# uSlices_v3_2.net
KiCad netlist of a schematic drawn in EAGLE
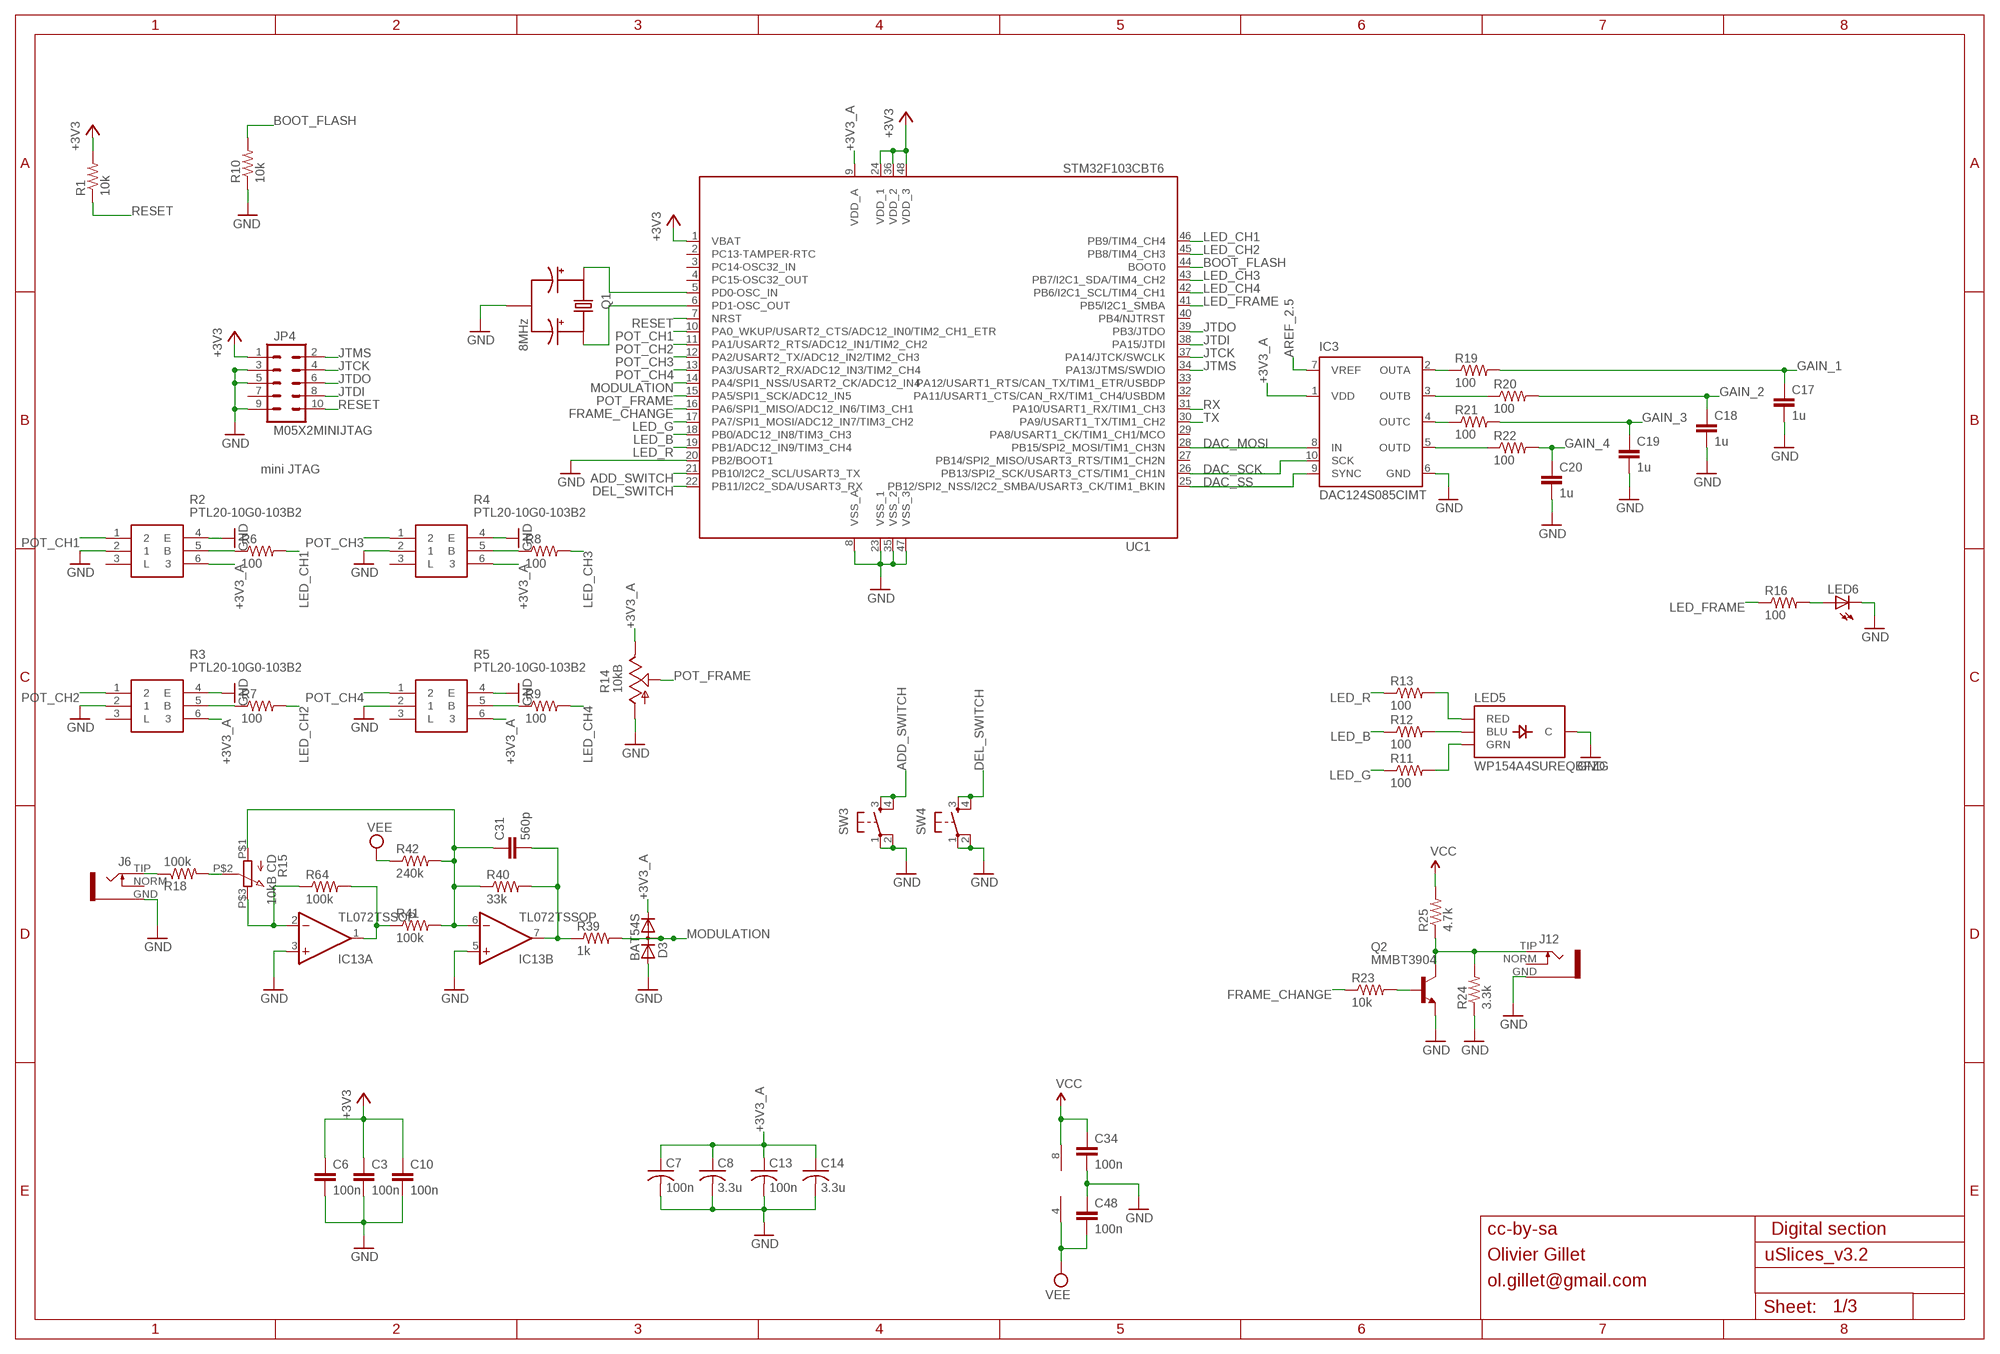
[diagram p0: schematic, sheet 1]
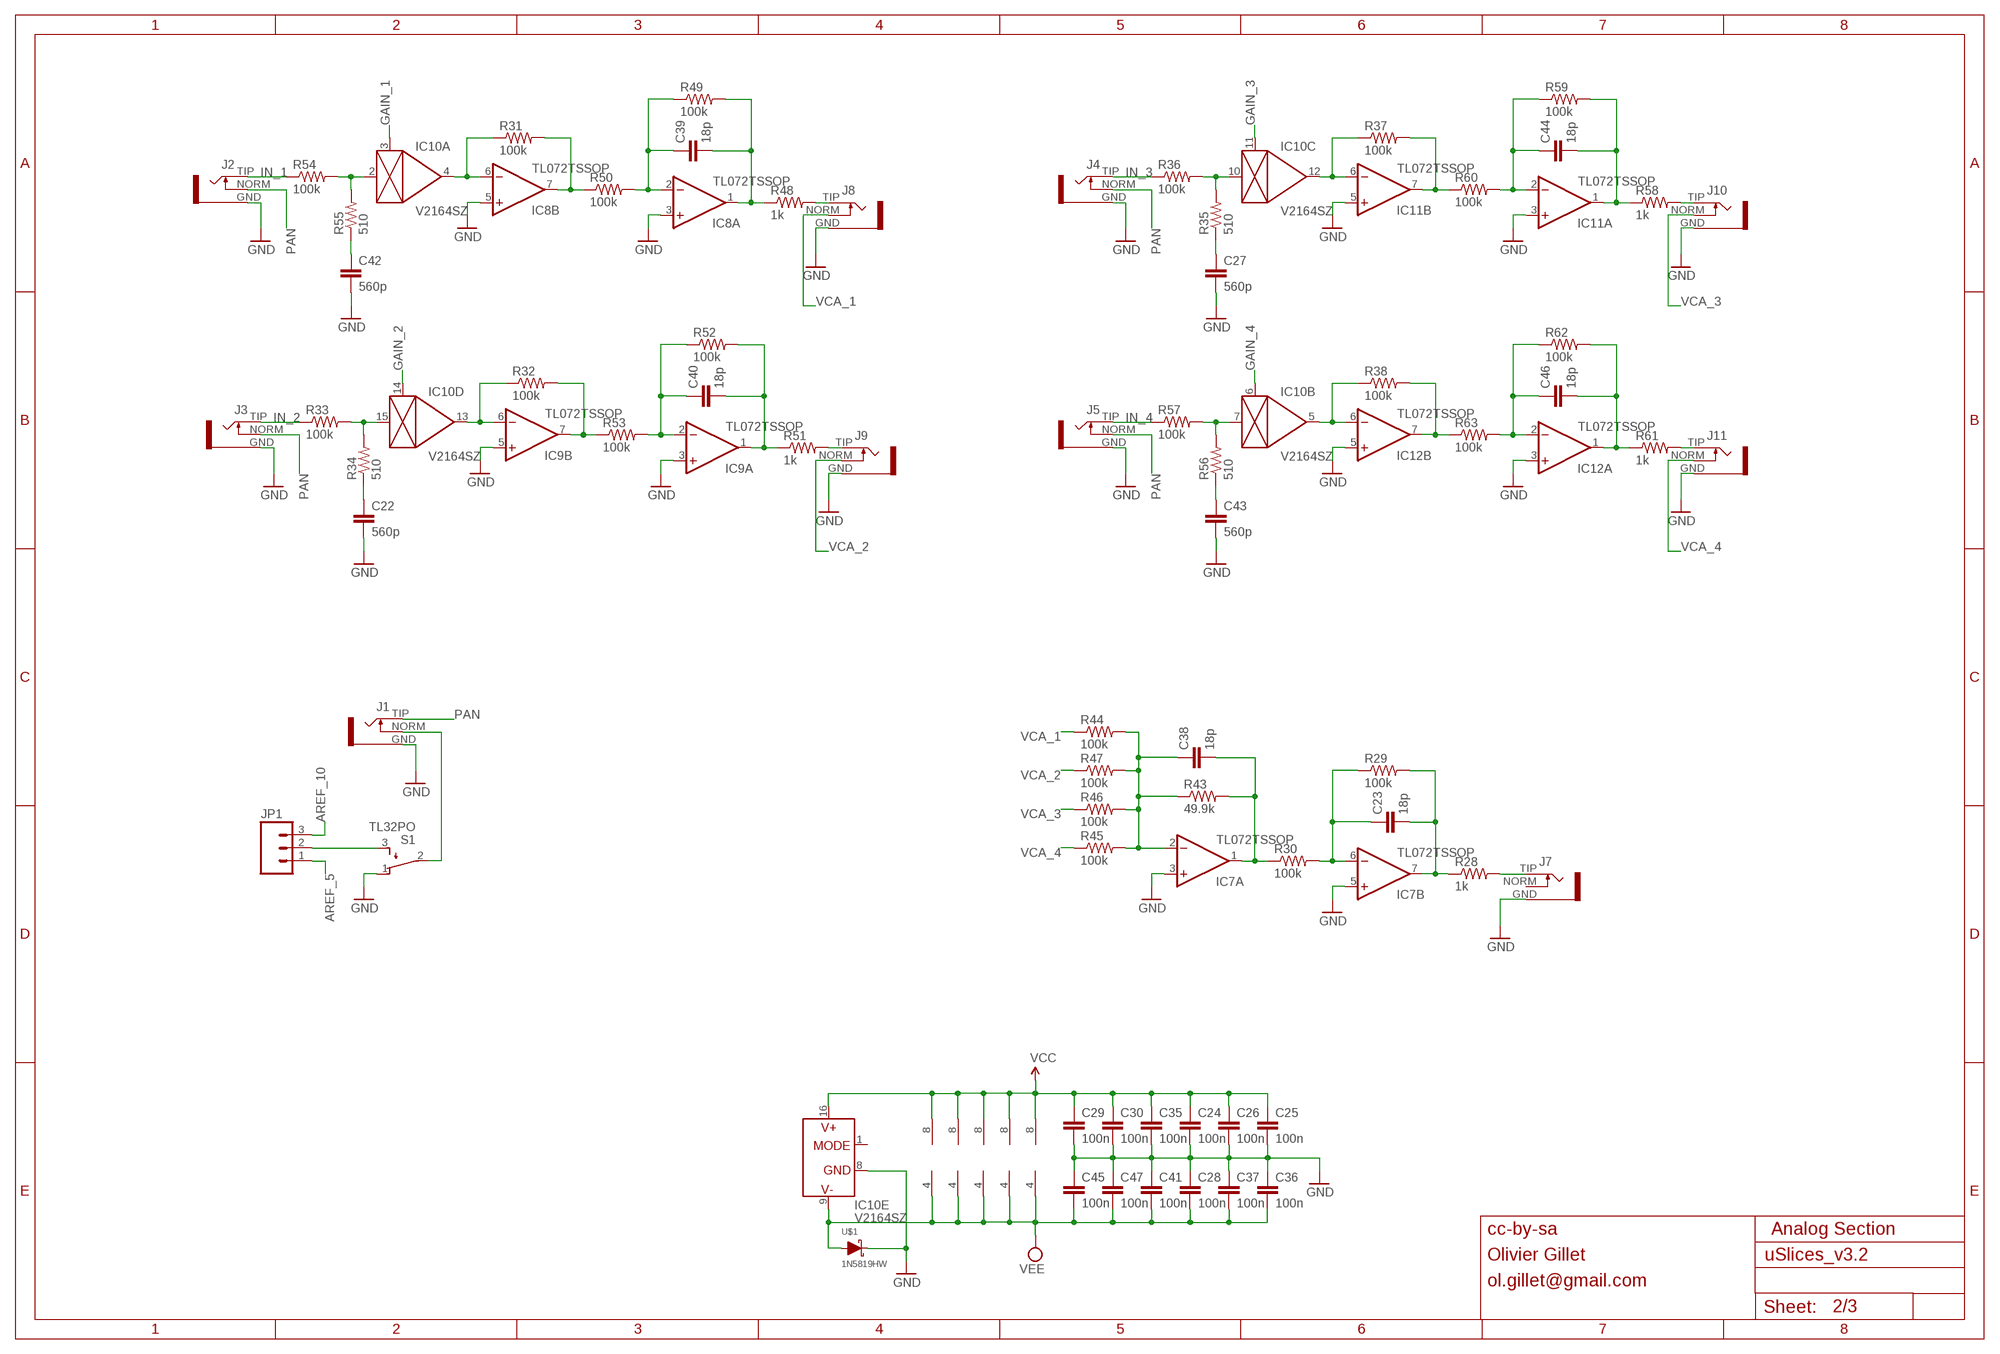
[diagram p1: schematic, sheet 2]
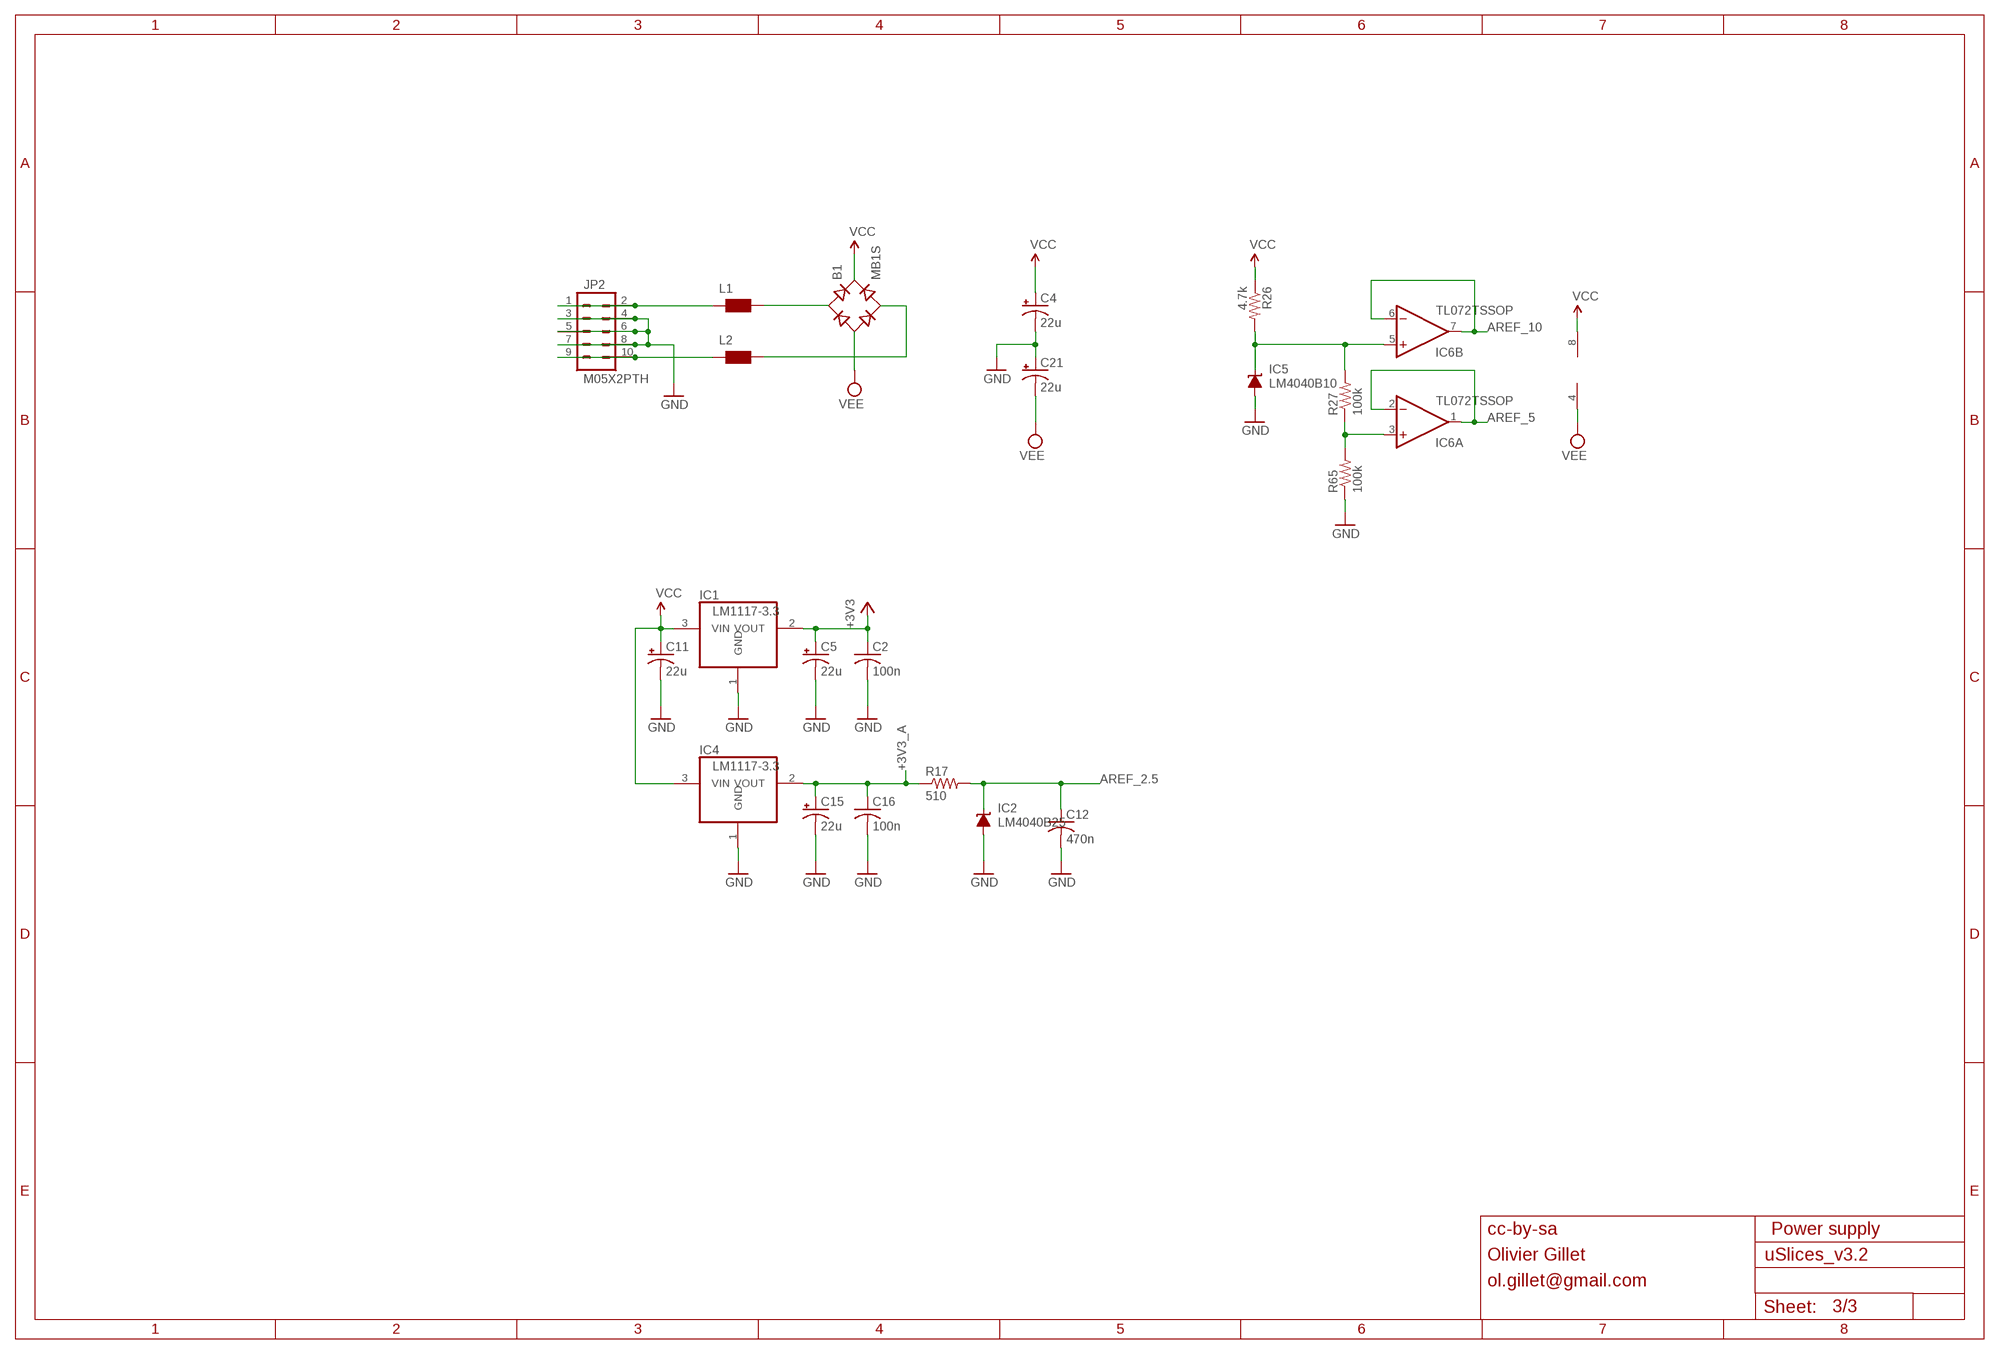
[diagram p2: schematic, sheet 3]

(export (version "E")
  (design (tool "Eeschema 10.0.6"))
  (components
    (comp (ref "C3")
      (value "100n")
      (footprint "eagle-import:PARTS_AMAN_RESISTOR_0603")
      (libsource (lib "eagle-import") (part "PARTS_AMAN_CAPACITOR"))
    )
    (comp (ref "C6")
      (value "100n")
      (footprint "eagle-import:PARTS_AMAN_RESISTOR_0603")
      (libsource (lib "eagle-import") (part "PARTS_AMAN_CAPACITOR"))
    )
    (comp (ref "C7")
      (value "100n")
      (footprint "eagle-import:C0603")
      (libsource (lib "eagle-import") (part "C-USC0603"))
    )
    (comp (ref "C8")
      (value "3.3u")
      (footprint "eagle-import:C0603")
      (libsource (lib "eagle-import") (part "C-USC0603"))
    )
    (comp (ref "C10")
      (value "100n")
      (footprint "eagle-import:PARTS_AMAN_RESISTOR_0603")
      (libsource (lib "eagle-import") (part "PARTS_AMAN_CAPACITOR"))
    )
    (comp (ref "C13")
      (value "100n")
      (footprint "eagle-import:C0603")
      (libsource (lib "eagle-import") (part "C-USC0603"))
    )
    (comp (ref "C14")
      (value "3.3u")
      (footprint "eagle-import:C0603")
      (libsource (lib "eagle-import") (part "C-USC0603"))
    )
    (comp (ref "C17")
      (value "1u")
      (footprint "eagle-import:PARTS_AMAN_RESISTOR_0603")
      (libsource (lib "eagle-import") (part "PARTS_AMAN_CAPACITOR"))
    )
    (comp (ref "C18")
      (value "1u")
      (footprint "eagle-import:PARTS_AMAN_RESISTOR_0603")
      (libsource (lib "eagle-import") (part "PARTS_AMAN_CAPACITOR"))
    )
    (comp (ref "C19")
      (value "1u")
      (footprint "eagle-import:PARTS_AMAN_RESISTOR_0603")
      (libsource (lib "eagle-import") (part "PARTS_AMAN_CAPACITOR"))
    )
    (comp (ref "C20")
      (value "1u")
      (footprint "eagle-import:PARTS_AMAN_RESISTOR_0603")
      (libsource (lib "eagle-import") (part "PARTS_AMAN_CAPACITOR"))
    )
    (comp (ref "C31")
      (value "560p")
      (footprint "eagle-import:PARTS_AMAN_RESISTOR_0603")
      (libsource (lib "eagle-import") (part "PARTS_AMAN_CAPACITOR"))
    )
    (comp (ref "C34")
      (value "100n")
      (footprint "eagle-import:PARTS_AMAN_RESISTOR_0603")
      (libsource (lib "eagle-import") (part "PARTS_AMAN_CAPACITOR"))
    )
    (comp (ref "C48")
      (value "100n")
      (footprint "eagle-import:PARTS_AMAN_RESISTOR_0603")
      (libsource (lib "eagle-import") (part "PARTS_AMAN_CAPACITOR"))
    )
    (comp (ref "D3")
      (value "BAT54S")
      (footprint "eagle-import:SOT23")
      (libsource (lib "eagle-import") (part "DIODE_2CACA-SOT23"))
    )
    (comp (ref "IC3")
      (value "DAC124S085CIMT")
      (footprint "eagle-import:MSOP10")
      (libsource (lib "eagle-import") (part "DAC124S085CIMT"))
    )
    (comp (ref "IC13")
      (value "TL072TSSOP")
      (footprint "eagle-import:TSSOP-8")
      (libsource (lib "eagle-import") (part "TL072TSSOP"))
    )
    (comp (ref "J6")
      (value "INSTRUO_S_JACK_S2_INV")
      (footprint "eagle-import:INSTRUO_S_JACK_S2_INV")
      (libsource (lib "eagle-import") (part "INSTRUO_S_JACK_S2_INV"))
    )
    (comp (ref "J12")
      (value "INSTRUO_S_JACK_S2_INV")
      (footprint "eagle-import:INSTRUO_S_JACK_S2_INV")
      (libsource (lib "eagle-import") (part "INSTRUO_S_JACK_S2_INV"))
    )
    (comp (ref "JP4")
      (value "M05X2MINIJTAG")
      (footprint "eagle-import:2X5-1.27")
      (libsource (lib "eagle-import") (part "M05X2MINIJTAG"))
    )
    (comp (ref "LED5")
      (value "WP154A4SUREQBFZG")
      (footprint "eagle-import:LED-TRICOLOR-THROUGHHOLE")
      (libsource (lib "eagle-import") (part "LED-TRICOLOR-THROUGHHOLE"))
    )
    (comp (ref "LED6")
      (value "LED3MM")
      (footprint "eagle-import:LED3MM")
      (libsource (lib "eagle-import") (part "LED3MM"))
    )
    (comp (ref "Q1")
      (value "8MHz")
      (footprint "eagle-import:INSTRUO_CRYSTAL_SMALLER")
      (libsource (lib "eagle-import") (part "INSTRUO_CRYSTAL_SMALLER"))
    )
    (comp (ref "Q2")
      (value "MMBT3904")
      (footprint "eagle-import:SOT23-BEC")
      (libsource (lib "eagle-import") (part "-NPN-SOT23-BECMMBT3904LT1"))
    )
    (comp (ref "R1")
      (value "10k")
      (footprint "eagle-import:PARTS_AMAN_RESISTOR_0603")
      (libsource (lib "eagle-import") (part "PARTS_AMAN_RESISTOR"))
    )
    (comp (ref "R2")
      (value "PTL20-10G0-103B2")
      (footprint "eagle-import:PTL2010G0103B2")
      (fields (field (name "ARROW_PART_NUMBER") "PTL30-10O1-103B2"))
      (libsource (lib "eagle-import") (part "PTL20-10G0-103B2"))
    )
    (comp (ref "R3")
      (value "PTL20-10G0-103B2")
      (footprint "eagle-import:PTL2010G0103B2")
      (fields (field (name "ARROW_PART_NUMBER") "PTL30-10O1-103B2"))
      (libsource (lib "eagle-import") (part "PTL20-10G0-103B2"))
    )
    (comp (ref "R4")
      (value "PTL20-10G0-103B2")
      (footprint "eagle-import:PTL2010G0103B2")
      (fields (field (name "ARROW_PART_NUMBER") "PTL30-10O1-103B2"))
      (libsource (lib "eagle-import") (part "PTL20-10G0-103B2"))
    )
    (comp (ref "R5")
      (value "PTL20-10G0-103B2")
      (footprint "eagle-import:PTL2010G0103B2")
      (fields (field (name "ARROW_PART_NUMBER") "PTL30-10O1-103B2"))
      (libsource (lib "eagle-import") (part "PTL20-10G0-103B2"))
    )
    (comp (ref "R6")
      (value "100")
      (footprint "eagle-import:PARTS_AMAN_RESISTOR_0603")
      (libsource (lib "eagle-import") (part "PARTS_AMAN_RESISTOR"))
    )
    (comp (ref "R7")
      (value "100")
      (footprint "eagle-import:PARTS_AMAN_RESISTOR_0603")
      (libsource (lib "eagle-import") (part "PARTS_AMAN_RESISTOR"))
    )
    (comp (ref "R8")
      (value "100")
      (footprint "eagle-import:PARTS_AMAN_RESISTOR_0603")
      (libsource (lib "eagle-import") (part "PARTS_AMAN_RESISTOR"))
    )
    (comp (ref "R9")
      (value "100")
      (footprint "eagle-import:PARTS_AMAN_RESISTOR_0603")
      (libsource (lib "eagle-import") (part "PARTS_AMAN_RESISTOR"))
    )
    (comp (ref "R10")
      (value "10k")
      (footprint "eagle-import:PARTS_AMAN_RESISTOR_0603")
      (libsource (lib "eagle-import") (part "PARTS_AMAN_RESISTOR"))
    )
    (comp (ref "R11")
      (value "100")
      (footprint "eagle-import:PARTS_AMAN_RESISTOR_0603")
      (libsource (lib "eagle-import") (part "PARTS_AMAN_RESISTOR"))
    )
    (comp (ref "R12")
      (value "100")
      (footprint "eagle-import:PARTS_AMAN_RESISTOR_0603")
      (libsource (lib "eagle-import") (part "PARTS_AMAN_RESISTOR"))
    )
    (comp (ref "R13")
      (value "100")
      (footprint "eagle-import:PARTS_AMAN_RESISTOR_0603")
      (libsource (lib "eagle-import") (part "PARTS_AMAN_RESISTOR"))
    )
    (comp (ref "R14")
      (value "10kB")
      (footprint "eagle-import:ALPS_POT_VERTICAL_PS")
      (libsource (lib "eagle-import") (part "POT_USVERTICAL_PS"))
    )
    (comp (ref "R15")
      (value "10kB CD")
      (footprint "eagle-import:INSTRUO_Q-POT2")
      (libsource (lib "eagle-import") (part "INSTRUO_Q-POT2"))
    )
    (comp (ref "R16")
      (value "100")
      (footprint "eagle-import:PARTS_AMAN_RESISTOR_0603")
      (libsource (lib "eagle-import") (part "PARTS_AMAN_RESISTOR"))
    )
    (comp (ref "R18")
      (value "100k")
      (footprint "eagle-import:R0603")
      (libsource (lib "eagle-import") (part "R-US_R0603"))
    )
    (comp (ref "R19")
      (value "100")
      (footprint "eagle-import:PARTS_AMAN_RESISTOR_0603")
      (libsource (lib "eagle-import") (part "PARTS_AMAN_RESISTOR"))
    )
    (comp (ref "R20")
      (value "100")
      (footprint "eagle-import:PARTS_AMAN_RESISTOR_0603")
      (libsource (lib "eagle-import") (part "PARTS_AMAN_RESISTOR"))
    )
    (comp (ref "R21")
      (value "100")
      (footprint "eagle-import:PARTS_AMAN_RESISTOR_0603")
      (libsource (lib "eagle-import") (part "PARTS_AMAN_RESISTOR"))
    )
    (comp (ref "R22")
      (value "100")
      (footprint "eagle-import:PARTS_AMAN_RESISTOR_0603")
      (libsource (lib "eagle-import") (part "PARTS_AMAN_RESISTOR"))
    )
    (comp (ref "R23")
      (value "10k")
      (footprint "eagle-import:PARTS_AMAN_RESISTOR_0603")
      (libsource (lib "eagle-import") (part "PARTS_AMAN_RESISTOR"))
    )
    (comp (ref "R24")
      (value "3.3k")
      (footprint "eagle-import:PARTS_AMAN_RESISTOR_0603")
      (libsource (lib "eagle-import") (part "PARTS_AMAN_RESISTOR"))
    )
    (comp (ref "R25")
      (value "4.7k")
      (footprint "eagle-import:PARTS_AMAN_RESISTOR_0603")
      (libsource (lib "eagle-import") (part "PARTS_AMAN_RESISTOR"))
    )
    (comp (ref "R39")
      (value "1k")
      (footprint "eagle-import:PARTS_AMAN_RESISTOR_0603")
      (libsource (lib "eagle-import") (part "PARTS_AMAN_RESISTOR"))
    )
    (comp (ref "R40")
      (value "33k")
      (footprint "eagle-import:PARTS_AMAN_RESISTOR_0603")
      (libsource (lib "eagle-import") (part "PARTS_AMAN_RESISTOR"))
    )
    (comp (ref "R41")
      (value "100k")
      (footprint "eagle-import:PARTS_AMAN_RESISTOR_0603")
      (libsource (lib "eagle-import") (part "PARTS_AMAN_RESISTOR"))
    )
    (comp (ref "R42")
      (value "240k")
      (footprint "eagle-import:PARTS_AMAN_RESISTOR_0603")
      (libsource (lib "eagle-import") (part "PARTS_AMAN_RESISTOR"))
    )
    (comp (ref "R64")
      (value "100k")
      (footprint "eagle-import:PARTS_AMAN_RESISTOR_0603")
      (libsource (lib "eagle-import") (part "PARTS_AMAN_RESISTOR"))
    )
    (comp (ref "SW3")
      (value "SPARKFUN_TAC_SWITCHPTH")
      (footprint "eagle-import:SPARKFUN_TACTILE-PTH")
      (libsource (lib "eagle-import") (part "SPARKFUN_TAC_SWITCHPTH"))
    )
    (comp (ref "SW4")
      (value "SPARKFUN_TAC_SWITCHPTH")
      (footprint "eagle-import:SPARKFUN_TACTILE-PTH")
      (libsource (lib "eagle-import") (part "SPARKFUN_TAC_SWITCHPTH"))
    )
    (comp (ref "UC1")
      (value "STM32F103CBT6")
      (footprint "eagle-import:LQFP48")
      (libsource (lib "eagle-import") (part "STM32F103CB"))
    )
    (comp (ref "B1")
      (value "MB1S")
      (footprint "eagle-import:SOIC-4")
      (libsource (lib "eagle-import") (part "MBS1"))
    )
    (comp (ref "C2")
      (value "100n")
      (footprint "eagle-import:C0603")
      (libsource (lib "eagle-import") (part "C-USC0603"))
    )
    (comp (ref "C4")
      (value "22u")
      (footprint "eagle-import:PANASONIC_C")
      (libsource (lib "eagle-import") (part "CPOL-USC"))
    )
    (comp (ref "C5")
      (value "22u")
      (footprint "eagle-import:PANASONIC_C")
      (libsource (lib "eagle-import") (part "CPOL-USC"))
    )
    (comp (ref "C11")
      (value "22u")
      (footprint "eagle-import:PANASONIC_C")
      (libsource (lib "eagle-import") (part "CPOL-USC"))
    )
    (comp (ref "C12")
      (value "470n")
      (footprint "eagle-import:C0603")
      (libsource (lib "eagle-import") (part "C-USC0603"))
    )
    (comp (ref "C15")
      (value "22u")
      (footprint "eagle-import:PANASONIC_C")
      (libsource (lib "eagle-import") (part "CPOL-USC"))
    )
    (comp (ref "C16")
      (value "100n")
      (footprint "eagle-import:C0603")
      (libsource (lib "eagle-import") (part "C-USC0603"))
    )
    (comp (ref "C21")
      (value "22u")
      (footprint "eagle-import:PANASONIC_C")
      (libsource (lib "eagle-import") (part "CPOL-USC"))
    )
    (comp (ref "IC1")
      (value "LM1117-3.3")
      (footprint "eagle-import:SOT223")
      (libsource (lib "eagle-import") (part "REG1117"))
    )
    (comp (ref "IC2")
      (value "LM4040B25")
      (footprint "eagle-import:DBZ_R-PDSO-G3")
      (libsource (lib "eagle-import") (part "LM4041DBZB12"))
    )
    (comp (ref "IC4")
      (value "LM1117-3.3")
      (footprint "eagle-import:SOT223")
      (libsource (lib "eagle-import") (part "REG1117"))
    )
    (comp (ref "IC5")
      (value "LM4040B10")
      (footprint "eagle-import:DBZ_R-PDSO-G3")
      (libsource (lib "eagle-import") (part "LM4041DBZB12"))
    )
    (comp (ref "IC6")
      (value "TL072TSSOP")
      (footprint "eagle-import:TSSOP-8")
      (libsource (lib "eagle-import") (part "TL072TSSOP"))
    )
    (comp (ref "JP2")
      (value "M05X2PTH")
      (footprint "eagle-import:AVR_ICSP")
      (libsource (lib "eagle-import") (part "M05X2PTH"))
    )
    (comp (ref "L1")
      (value "WUERTH-ELEKTRONIK_WE-CBF_0603")
      (footprint "eagle-import:WUERTH-ELEKTRONIK_0603")
      (libsource (lib "eagle-import") (part "WUERTH-ELEKTRONIK_WE-CBF_0603"))
    )
    (comp (ref "L2")
      (value "WUERTH-ELEKTRONIK_WE-CBF_0603")
      (footprint "eagle-import:WUERTH-ELEKTRONIK_0603")
      (libsource (lib "eagle-import") (part "WUERTH-ELEKTRONIK_WE-CBF_0603"))
    )
    (comp (ref "R17")
      (value "510")
      (footprint "eagle-import:R0603")
      (libsource (lib "eagle-import") (part "R-US_R0603"))
    )
    (comp (ref "R26")
      (value "4.7k")
      (footprint "eagle-import:R0603")
      (libsource (lib "eagle-import") (part "R-US_R0603"))
    )
    (comp (ref "R27")
      (value "100k")
      (footprint "eagle-import:R0603")
      (libsource (lib "eagle-import") (part "R-US_R0603"))
    )
    (comp (ref "R65")
      (value "100k")
      (footprint "eagle-import:R0603")
      (libsource (lib "eagle-import") (part "R-US_R0603"))
    )
    (comp (ref "C22")
      (value "560p")
      (footprint "eagle-import:PARTS_AMAN_RESISTOR_0603")
      (libsource (lib "eagle-import") (part "PARTS_AMAN_CAPACITOR"))
    )
    (comp (ref "C23")
      (value "18p")
      (footprint "eagle-import:PARTS_AMAN_RESISTOR_0603")
      (libsource (lib "eagle-import") (part "PARTS_AMAN_CAPACITOR"))
    )
    (comp (ref "C24")
      (value "100n")
      (footprint "eagle-import:PARTS_AMAN_RESISTOR_0603")
      (libsource (lib "eagle-import") (part "PARTS_AMAN_CAPACITOR"))
    )
    (comp (ref "C25")
      (value "100n")
      (footprint "eagle-import:PARTS_AMAN_RESISTOR_0603")
      (libsource (lib "eagle-import") (part "PARTS_AMAN_CAPACITOR"))
    )
    (comp (ref "C26")
      (value "100n")
      (footprint "eagle-import:PARTS_AMAN_RESISTOR_0603")
      (libsource (lib "eagle-import") (part "PARTS_AMAN_CAPACITOR"))
    )
    (comp (ref "C27")
      (value "560p")
      (footprint "eagle-import:PARTS_AMAN_RESISTOR_0603")
      (libsource (lib "eagle-import") (part "PARTS_AMAN_CAPACITOR"))
    )
    (comp (ref "C28")
      (value "100n")
      (footprint "eagle-import:PARTS_AMAN_RESISTOR_0603")
      (libsource (lib "eagle-import") (part "PARTS_AMAN_CAPACITOR"))
    )
    (comp (ref "C29")
      (value "100n")
      (footprint "eagle-import:PARTS_AMAN_RESISTOR_0603")
      (libsource (lib "eagle-import") (part "PARTS_AMAN_CAPACITOR"))
    )
    (comp (ref "C30")
      (value "100n")
      (footprint "eagle-import:PARTS_AMAN_RESISTOR_0603")
      (libsource (lib "eagle-import") (part "PARTS_AMAN_CAPACITOR"))
    )
    (comp (ref "C35")
      (value "100n")
      (footprint "eagle-import:PARTS_AMAN_RESISTOR_0603")
      (libsource (lib "eagle-import") (part "PARTS_AMAN_CAPACITOR"))
    )
    (comp (ref "C36")
      (value "100n")
      (footprint "eagle-import:PARTS_AMAN_RESISTOR_0603")
      (libsource (lib "eagle-import") (part "PARTS_AMAN_CAPACITOR"))
    )
    (comp (ref "C37")
      (value "100n")
      (footprint "eagle-import:PARTS_AMAN_RESISTOR_0603")
      (libsource (lib "eagle-import") (part "PARTS_AMAN_CAPACITOR"))
    )
    (comp (ref "C38")
      (value "18p")
      (footprint "eagle-import:PARTS_AMAN_RESISTOR_0603")
      (libsource (lib "eagle-import") (part "PARTS_AMAN_CAPACITOR"))
    )
    (comp (ref "C39")
      (value "18p")
      (footprint "eagle-import:PARTS_AMAN_RESISTOR_0603")
      (libsource (lib "eagle-import") (part "PARTS_AMAN_CAPACITOR"))
    )
    (comp (ref "C40")
      (value "18p")
      (footprint "eagle-import:PARTS_AMAN_RESISTOR_0603")
      (libsource (lib "eagle-import") (part "PARTS_AMAN_CAPACITOR"))
    )
    (comp (ref "C41")
      (value "100n")
      (footprint "eagle-import:PARTS_AMAN_RESISTOR_0603")
      (libsource (lib "eagle-import") (part "PARTS_AMAN_CAPACITOR"))
    )
    (comp (ref "C42")
      (value "560p")
      (footprint "eagle-import:PARTS_AMAN_RESISTOR_0603")
      (libsource (lib "eagle-import") (part "PARTS_AMAN_CAPACITOR"))
    )
    (comp (ref "C43")
      (value "560p")
      (footprint "eagle-import:PARTS_AMAN_RESISTOR_0603")
      (libsource (lib "eagle-import") (part "PARTS_AMAN_CAPACITOR"))
    )
    (comp (ref "C44")
      (value "18p")
      (footprint "eagle-import:PARTS_AMAN_RESISTOR_0603")
      (libsource (lib "eagle-import") (part "PARTS_AMAN_CAPACITOR"))
    )
    (comp (ref "C45")
      (value "100n")
      (footprint "eagle-import:PARTS_AMAN_RESISTOR_0603")
      (libsource (lib "eagle-import") (part "PARTS_AMAN_CAPACITOR"))
    )
    (comp (ref "C46")
      (value "18p")
      (footprint "eagle-import:PARTS_AMAN_RESISTOR_0603")
      (libsource (lib "eagle-import") (part "PARTS_AMAN_CAPACITOR"))
    )
    (comp (ref "C47")
      (value "100n")
      (footprint "eagle-import:PARTS_AMAN_RESISTOR_0603")
      (libsource (lib "eagle-import") (part "PARTS_AMAN_CAPACITOR"))
    )
    (comp (ref "IC7")
      (value "TL072TSSOP")
      (footprint "eagle-import:TSSOP-8")
      (libsource (lib "eagle-import") (part "TL072TSSOP"))
    )
    (comp (ref "IC8")
      (value "TL072TSSOP")
      (footprint "eagle-import:TSSOP-8")
      (libsource (lib "eagle-import") (part "TL072TSSOP"))
    )
    (comp (ref "IC9")
      (value "TL072TSSOP")
      (footprint "eagle-import:TSSOP-8")
      (libsource (lib "eagle-import") (part "TL072TSSOP"))
    )
    (comp (ref "IC10")
      (value "V2164SZ")
      (footprint "eagle-import:SOIC16N")
      (libsource (lib "eagle-import") (part "SSM2164S"))
    )
    (comp (ref "IC11")
      (value "TL072TSSOP")
      (footprint "eagle-import:TSSOP-8")
      (libsource (lib "eagle-import") (part "TL072TSSOP"))
    )
    (comp (ref "IC12")
      (value "TL072TSSOP")
      (footprint "eagle-import:TSSOP-8")
      (libsource (lib "eagle-import") (part "TL072TSSOP"))
    )
    (comp (ref "J1")
      (value "INSTRUO_S_JACK_S2_INV")
      (footprint "eagle-import:INSTRUO_S_JACK_S2_INV")
      (libsource (lib "eagle-import") (part "INSTRUO_S_JACK_S2_INV"))
    )
    (comp (ref "J2")
      (value "INSTRUO_S_JACK_S2_INV")
      (footprint "eagle-import:INSTRUO_S_JACK_S2_INV")
      (libsource (lib "eagle-import") (part "INSTRUO_S_JACK_S2_INV"))
    )
    (comp (ref "J3")
      (value "INSTRUO_S_JACK_S2_INV")
      (footprint "eagle-import:INSTRUO_S_JACK_S2_INV")
      (libsource (lib "eagle-import") (part "INSTRUO_S_JACK_S2_INV"))
    )
    (comp (ref "J4")
      (value "INSTRUO_S_JACK_S2_INV")
      (footprint "eagle-import:INSTRUO_S_JACK_S2_INV")
      (libsource (lib "eagle-import") (part "INSTRUO_S_JACK_S2_INV"))
    )
    (comp (ref "J5")
      (value "INSTRUO_S_JACK_S2_INV")
      (footprint "eagle-import:INSTRUO_S_JACK_S2_INV")
      (libsource (lib "eagle-import") (part "INSTRUO_S_JACK_S2_INV"))
    )
    (comp (ref "J7")
      (value "INSTRUO_S_JACK_S2_INV")
      (footprint "eagle-import:INSTRUO_S_JACK_S2_INV")
      (libsource (lib "eagle-import") (part "INSTRUO_S_JACK_S2_INV"))
    )
    (comp (ref "J8")
      (value "INSTRUO_S_JACK_S2_INV")
      (footprint "eagle-import:INSTRUO_S_JACK_S2_INV")
      (libsource (lib "eagle-import") (part "INSTRUO_S_JACK_S2_INV"))
    )
    (comp (ref "J9")
      (value "INSTRUO_S_JACK_S2_INV")
      (footprint "eagle-import:INSTRUO_S_JACK_S2_INV")
      (libsource (lib "eagle-import") (part "INSTRUO_S_JACK_S2_INV"))
    )
    (comp (ref "J10")
      (value "INSTRUO_S_JACK_S2_INV")
      (footprint "eagle-import:INSTRUO_S_JACK_S2_INV")
      (libsource (lib "eagle-import") (part "INSTRUO_S_JACK_S2_INV"))
    )
    (comp (ref "J11")
      (value "INSTRUO_S_JACK_S2_INV")
      (footprint "eagle-import:INSTRUO_S_JACK_S2_INV")
      (libsource (lib "eagle-import") (part "INSTRUO_S_JACK_S2_INV"))
    )
    (comp (ref "JP1")
      (value "M03PTH")
      (footprint "eagle-import:1X03")
      (libsource (lib "eagle-import") (part "M03PTH"))
    )
    (comp (ref "R28")
      (value "1k")
      (footprint "eagle-import:PARTS_AMAN_RESISTOR_0603")
      (libsource (lib "eagle-import") (part "PARTS_AMAN_RESISTOR"))
    )
    (comp (ref "R29")
      (value "100k")
      (footprint "eagle-import:PARTS_AMAN_RESISTOR_0603")
      (libsource (lib "eagle-import") (part "PARTS_AMAN_RESISTOR"))
    )
    (comp (ref "R30")
      (value "100k")
      (footprint "eagle-import:PARTS_AMAN_RESISTOR_0603")
      (libsource (lib "eagle-import") (part "PARTS_AMAN_RESISTOR"))
    )
    (comp (ref "R31")
      (value "100k")
      (footprint "eagle-import:PARTS_AMAN_RESISTOR_0603")
      (libsource (lib "eagle-import") (part "PARTS_AMAN_RESISTOR"))
    )
    (comp (ref "R32")
      (value "100k")
      (footprint "eagle-import:PARTS_AMAN_RESISTOR_0603")
      (libsource (lib "eagle-import") (part "PARTS_AMAN_RESISTOR"))
    )
    (comp (ref "R33")
      (value "100k")
      (footprint "eagle-import:PARTS_AMAN_RESISTOR_0603")
      (libsource (lib "eagle-import") (part "PARTS_AMAN_RESISTOR"))
    )
    (comp (ref "R34")
      (value "510")
      (footprint "eagle-import:PARTS_AMAN_RESISTOR_0603")
      (libsource (lib "eagle-import") (part "PARTS_AMAN_RESISTOR"))
    )
    (comp (ref "R35")
      (value "510")
      (footprint "eagle-import:PARTS_AMAN_RESISTOR_0603")
      (libsource (lib "eagle-import") (part "PARTS_AMAN_RESISTOR"))
    )
    (comp (ref "R36")
      (value "100k")
      (footprint "eagle-import:PARTS_AMAN_RESISTOR_0603")
      (libsource (lib "eagle-import") (part "PARTS_AMAN_RESISTOR"))
    )
    (comp (ref "R37")
      (value "100k")
      (footprint "eagle-import:PARTS_AMAN_RESISTOR_0603")
      (libsource (lib "eagle-import") (part "PARTS_AMAN_RESISTOR"))
    )
    (comp (ref "R38")
      (value "100k")
      (footprint "eagle-import:PARTS_AMAN_RESISTOR_0603")
      (libsource (lib "eagle-import") (part "PARTS_AMAN_RESISTOR"))
    )
    (comp (ref "R43")
      (value "49.9k")
      (footprint "eagle-import:PARTS_AMAN_RESISTOR_0603")
      (libsource (lib "eagle-import") (part "PARTS_AMAN_RESISTOR"))
    )
    (comp (ref "R44")
      (value "100k")
      (footprint "eagle-import:PARTS_AMAN_RESISTOR_0603")
      (libsource (lib "eagle-import") (part "PARTS_AMAN_RESISTOR"))
    )
    (comp (ref "R45")
      (value "100k")
      (footprint "eagle-import:PARTS_AMAN_RESISTOR_0603")
      (libsource (lib "eagle-import") (part "PARTS_AMAN_RESISTOR"))
    )
    (comp (ref "R46")
      (value "100k")
      (footprint "eagle-import:PARTS_AMAN_RESISTOR_0603")
      (libsource (lib "eagle-import") (part "PARTS_AMAN_RESISTOR"))
    )
    (comp (ref "R47")
      (value "100k")
      (footprint "eagle-import:PARTS_AMAN_RESISTOR_0603")
      (libsource (lib "eagle-import") (part "PARTS_AMAN_RESISTOR"))
    )
    (comp (ref "R48")
      (value "1k")
      (footprint "eagle-import:PARTS_AMAN_RESISTOR_0603")
      (libsource (lib "eagle-import") (part "PARTS_AMAN_RESISTOR"))
    )
    (comp (ref "R49")
      (value "100k")
      (footprint "eagle-import:PARTS_AMAN_RESISTOR_0603")
      (libsource (lib "eagle-import") (part "PARTS_AMAN_RESISTOR"))
    )
    (comp (ref "R50")
      (value "100k")
      (footprint "eagle-import:PARTS_AMAN_RESISTOR_0603")
      (libsource (lib "eagle-import") (part "PARTS_AMAN_RESISTOR"))
    )
    (comp (ref "R51")
      (value "1k")
      (footprint "eagle-import:PARTS_AMAN_RESISTOR_0603")
      (libsource (lib "eagle-import") (part "PARTS_AMAN_RESISTOR"))
    )
    (comp (ref "R52")
      (value "100k")
      (footprint "eagle-import:PARTS_AMAN_RESISTOR_0603")
      (libsource (lib "eagle-import") (part "PARTS_AMAN_RESISTOR"))
    )
    (comp (ref "R53")
      (value "100k")
      (footprint "eagle-import:PARTS_AMAN_RESISTOR_0603")
      (libsource (lib "eagle-import") (part "PARTS_AMAN_RESISTOR"))
    )
    (comp (ref "R54")
      (value "100k")
      (footprint "eagle-import:PARTS_AMAN_RESISTOR_0603")
      (libsource (lib "eagle-import") (part "PARTS_AMAN_RESISTOR"))
    )
    (comp (ref "R55")
      (value "510")
      (footprint "eagle-import:PARTS_AMAN_RESISTOR_0603")
      (libsource (lib "eagle-import") (part "PARTS_AMAN_RESISTOR"))
    )
    (comp (ref "R56")
      (value "510")
      (footprint "eagle-import:PARTS_AMAN_RESISTOR_0603")
      (libsource (lib "eagle-import") (part "PARTS_AMAN_RESISTOR"))
    )
    (comp (ref "R57")
      (value "100k")
      (footprint "eagle-import:PARTS_AMAN_RESISTOR_0603")
      (libsource (lib "eagle-import") (part "PARTS_AMAN_RESISTOR"))
    )
    (comp (ref "R58")
      (value "1k")
      (footprint "eagle-import:PARTS_AMAN_RESISTOR_0603")
      (libsource (lib "eagle-import") (part "PARTS_AMAN_RESISTOR"))
    )
    (comp (ref "R59")
      (value "100k")
      (footprint "eagle-import:PARTS_AMAN_RESISTOR_0603")
      (libsource (lib "eagle-import") (part "PARTS_AMAN_RESISTOR"))
    )
    (comp (ref "R60")
      (value "100k")
      (footprint "eagle-import:PARTS_AMAN_RESISTOR_0603")
      (libsource (lib "eagle-import") (part "PARTS_AMAN_RESISTOR"))
    )
    (comp (ref "R61")
      (value "1k")
      (footprint "eagle-import:PARTS_AMAN_RESISTOR_0603")
      (libsource (lib "eagle-import") (part "PARTS_AMAN_RESISTOR"))
    )
    (comp (ref "R62")
      (value "100k")
      (footprint "eagle-import:PARTS_AMAN_RESISTOR_0603")
      (libsource (lib "eagle-import") (part "PARTS_AMAN_RESISTOR"))
    )
    (comp (ref "R63")
      (value "100k")
      (footprint "eagle-import:PARTS_AMAN_RESISTOR_0603")
      (libsource (lib "eagle-import") (part "PARTS_AMAN_RESISTOR"))
    )
    (comp (ref "S1")
      (value "TL32PO")
      (footprint "eagle-import:TL3XPO")
      (libsource (lib "eagle-import") (part "TL32PO"))
    )
    (comp (ref "U$1")
      (value "1N5819HW")
      (footprint "eagle-import:SOD123")
      (fields (field (name "MPN") "1N5819HW-7-F"))
      (libsource (lib "eagle-import") (part "1N5819HW"))
    )
  )
  (nets
    (net (code "1") (name "+3V3") (class "Default")
      (node (ref "C10") (pin "1") (pinfunction "1_1") (pintype "passive"))
      (node (ref "C2") (pin "1") (pinfunction "1_1") (pintype "passive"))
      (node (ref "C3") (pin "1") (pinfunction "1_1") (pintype "passive"))
      (node (ref "C5") (pin "+") (pinfunction "+_+") (pintype "passive"))
      (node (ref "C6") (pin "1") (pinfunction "1_1") (pintype "passive"))
      (node (ref "IC1") (pin "2") (pinfunction "VOUT_2") (pintype "output"))
      (node (ref "JP4") (pin "1") (pinfunction "1_1") (pintype "passive"))
      (node (ref "R1") (pin "2") (pinfunction "2_2") (pintype "passive"))
      (node (ref "UC1") (pin "1") (pinfunction "VBAT_1") (pintype "power_in"))
      (node (ref "UC1") (pin "24") (pinfunction "VDD_1_24") (pintype "power_in"))
      (node (ref "UC1") (pin "36") (pinfunction "VDD_2_36") (pintype "power_in"))
      (node (ref "UC1") (pin "48") (pinfunction "VDD_3_48") (pintype "power_in"))
    )
    (net (code "2") (name "+3V3_A") (class "Default")
      (node (ref "C13") (pin "1") (pinfunction "1_1") (pintype "passive"))
      (node (ref "C14") (pin "1") (pinfunction "1_1") (pintype "passive"))
      (node (ref "C15") (pin "+") (pinfunction "+_+") (pintype "passive"))
      (node (ref "C16") (pin "1") (pinfunction "1_1") (pintype "passive"))
      (node (ref "C7") (pin "1") (pinfunction "1_1") (pintype "passive"))
      (node (ref "C8") (pin "1") (pinfunction "1_1") (pintype "passive"))
      (node (ref "D3") (pin "2") (pinfunction "C_2") (pintype "passive"))
      (node (ref "IC3") (pin "1") (pinfunction "VDD_1") (pintype "power_in"))
      (node (ref "IC4") (pin "2") (pinfunction "VOUT_2") (pintype "output"))
      (node (ref "R14") (pin "P$1") (pinfunction "E_P$1") (pintype "passive"))
      (node (ref "R17") (pin "1") (pinfunction "1_1") (pintype "passive"))
      (node (ref "R2") (pin "6") (pinfunction "3_6") (pintype "bidirectional"))
      (node (ref "R3") (pin "6") (pinfunction "3_6") (pintype "bidirectional"))
      (node (ref "R4") (pin "6") (pinfunction "3_6") (pintype "bidirectional"))
      (node (ref "R5") (pin "6") (pinfunction "3_6") (pintype "bidirectional"))
      (node (ref "UC1") (pin "9") (pinfunction "VDD_A_9") (pintype "power_in"))
    )
    (net (code "3") (name "ADD_SWITCH") (class "Default")
      (node (ref "SW3") (pin "3") (pinfunction "3_3") (pintype "passive"))
      (node (ref "SW3") (pin "4") (pinfunction "4_4") (pintype "passive"))
      (node (ref "UC1") (pin "21") (pinfunction "PB10/I2C2_SCL/USART3_TX_21") (pintype "input"))
    )
    (net (code "4") (name "AREF_2.5") (class "Default")
      (node (ref "C12") (pin "1") (pinfunction "1_1") (pintype "passive"))
      (node (ref "IC2") (pin "1") (pinfunction "C_1") (pintype "passive"))
      (node (ref "IC3") (pin "7") (pinfunction "VREF_7") (pintype "bidirectional"))
      (node (ref "R17") (pin "2") (pinfunction "2_2") (pintype "passive"))
    )
    (net (code "5") (name "AREF_5") (class "Default")
      (node (ref "IC6") (pin "1") (pinfunction "OUT_1") (pintype "output"))
      (node (ref "IC6") (pin "2") (pinfunction "-IN_2") (pintype "input"))
      (node (ref "JP1") (pin "1") (pinfunction "1_1") (pintype "passive"))
    )
    (net (code "6") (name "AREF_10") (class "Default")
      (node (ref "IC6") (pin "6") (pinfunction "-IN_6") (pintype "input"))
      (node (ref "IC6") (pin "7") (pinfunction "OUT_7") (pintype "output"))
      (node (ref "JP1") (pin "3") (pinfunction "3_3") (pintype "passive"))
    )
    (net (code "7") (name "BOOT_FLASH") (class "Default")
      (node (ref "R10") (pin "2") (pinfunction "2_2") (pintype "passive"))
      (node (ref "UC1") (pin "44") (pinfunction "BOOT0_44") (pintype "input"))
    )
    (net (code "8") (name "DAC_MOSI") (class "Default")
      (node (ref "IC3") (pin "8") (pinfunction "IN_8") (pintype "input"))
      (node (ref "UC1") (pin "28") (pinfunction "PB15/SPI2_MOSI/TIM1_CH3N_28") (pintype "input"))
    )
    (net (code "9") (name "DAC_SCK") (class "Default")
      (node (ref "IC3") (pin "10") (pinfunction "SCK_10") (pintype "input"))
      (node (ref "UC1") (pin "26") (pinfunction "PB13/SPI2_SCK/USART3_CTS/TIM1_CH1N_26") (pintype "input"))
    )
    (net (code "10") (name "DAC_SS") (class "Default")
      (node (ref "IC3") (pin "9") (pinfunction "SYNC_9") (pintype "input"))
      (node (ref "UC1") (pin "25") (pinfunction "PB12/SPI2_NSS/I2C2_SMBA/USART3_CK/TIM1_BKIN_25") (pintype "input"))
    )
    (net (code "11") (name "DEL_SWITCH") (class "Default")
      (node (ref "SW4") (pin "3") (pinfunction "3_3") (pintype "passive"))
      (node (ref "SW4") (pin "4") (pinfunction "4_4") (pintype "passive"))
      (node (ref "UC1") (pin "22") (pinfunction "PB11/I2C2_SDA/USART3_RX_22") (pintype "input"))
    )
    (net (code "12") (name "FRAME_CHANGE") (class "Default")
      (node (ref "R23") (pin "1") (pinfunction "1_1") (pintype "passive"))
      (node (ref "UC1") (pin "16") (pinfunction "PA6/SPI1_MISO/ADC12_IN6/TIM3_CH1_16") (pintype "bidirectional"))
    )
    (net (code "13") (name "GAIN_1") (class "Default")
      (node (ref "C17") (pin "1") (pinfunction "1_1") (pintype "passive"))
      (node (ref "IC10") (pin "3") (pinfunction "CTRL_3") (pintype "input"))
      (node (ref "R19") (pin "2") (pinfunction "2_2") (pintype "passive"))
    )
    (net (code "14") (name "GAIN_2") (class "Default")
      (node (ref "C18") (pin "1") (pinfunction "1_1") (pintype "passive"))
      (node (ref "IC10") (pin "14") (pinfunction "CTRL_14") (pintype "input"))
      (node (ref "R20") (pin "2") (pinfunction "2_2") (pintype "passive"))
    )
    (net (code "15") (name "GAIN_3") (class "Default")
      (node (ref "C19") (pin "1") (pinfunction "1_1") (pintype "passive"))
      (node (ref "IC10") (pin "11") (pinfunction "CTRL_11") (pintype "input"))
      (node (ref "R21") (pin "2") (pinfunction "2_2") (pintype "passive"))
    )
    (net (code "16") (name "GAIN_4") (class "Default")
      (node (ref "C20") (pin "1") (pinfunction "1_1") (pintype "passive"))
      (node (ref "IC10") (pin "6") (pinfunction "CTRL_6") (pintype "input"))
      (node (ref "R22") (pin "2") (pinfunction "2_2") (pintype "passive"))
    )
    (net (code "17") (name "GND") (class "Default")
      (node (ref "C10") (pin "2") (pinfunction "2_2") (pintype "passive"))
      (node (ref "C11") (pin "-") (pinfunction "-_-") (pintype "passive"))
      (node (ref "C12") (pin "2") (pinfunction "2_2") (pintype "passive"))
      (node (ref "C13") (pin "2") (pinfunction "2_2") (pintype "passive"))
      (node (ref "C14") (pin "2") (pinfunction "2_2") (pintype "passive"))
      (node (ref "C15") (pin "-") (pinfunction "-_-") (pintype "passive"))
      (node (ref "C16") (pin "2") (pinfunction "2_2") (pintype "passive"))
      (node (ref "C17") (pin "2") (pinfunction "2_2") (pintype "passive"))
      (node (ref "C18") (pin "2") (pinfunction "2_2") (pintype "passive"))
      (node (ref "C19") (pin "2") (pinfunction "2_2") (pintype "passive"))
      (node (ref "C2") (pin "2") (pinfunction "2_2") (pintype "passive"))
      (node (ref "C20") (pin "2") (pinfunction "2_2") (pintype "passive"))
      (node (ref "C21") (pin "+") (pinfunction "+_+") (pintype "passive"))
      (node (ref "C22") (pin "2") (pinfunction "2_2") (pintype "passive"))
      (node (ref "C24") (pin "2") (pinfunction "2_2") (pintype "passive"))
      (node (ref "C25") (pin "2") (pinfunction "2_2") (pintype "passive"))
      (node (ref "C26") (pin "2") (pinfunction "2_2") (pintype "passive"))
      (node (ref "C27") (pin "2") (pinfunction "2_2") (pintype "passive"))
      (node (ref "C28") (pin "1") (pinfunction "1_1") (pintype "passive"))
      (node (ref "C29") (pin "2") (pinfunction "2_2") (pintype "passive"))
      (node (ref "C3") (pin "2") (pinfunction "2_2") (pintype "passive"))
      (node (ref "C30") (pin "2") (pinfunction "2_2") (pintype "passive"))
      (node (ref "C34") (pin "2") (pinfunction "2_2") (pintype "passive"))
      (node (ref "C35") (pin "2") (pinfunction "2_2") (pintype "passive"))
      (node (ref "C36") (pin "1") (pinfunction "1_1") (pintype "passive"))
      (node (ref "C37") (pin "1") (pinfunction "1_1") (pintype "passive"))
      (node (ref "C4") (pin "-") (pinfunction "-_-") (pintype "passive"))
      (node (ref "C41") (pin "1") (pinfunction "1_1") (pintype "passive"))
      (node (ref "C42") (pin "2") (pinfunction "2_2") (pintype "passive"))
      (node (ref "C43") (pin "2") (pinfunction "2_2") (pintype "passive"))
      (node (ref "C45") (pin "1") (pinfunction "1_1") (pintype "passive"))
      (node (ref "C47") (pin "1") (pinfunction "1_1") (pintype "passive"))
      (node (ref "C48") (pin "1") (pinfunction "1_1") (pintype "passive"))
      (node (ref "C5") (pin "-") (pinfunction "-_-") (pintype "passive"))
      (node (ref "C6") (pin "2") (pinfunction "2_2") (pintype "passive"))
      (node (ref "C7") (pin "2") (pinfunction "2_2") (pintype "passive"))
      (node (ref "C8") (pin "2") (pinfunction "2_2") (pintype "passive"))
      (node (ref "D3") (pin "1") (pinfunction "A_1") (pintype "passive"))
      (node (ref "IC1") (pin "1") (pinfunction "GND_1") (pintype "power_in"))
      (node (ref "IC10") (pin "8") (pinfunction "GND_8") (pintype "power_in"))
      (node (ref "IC11") (pin "3") (pinfunction "+IN_3") (pintype "input"))
      (node (ref "IC11") (pin "5") (pinfunction "+IN_5") (pintype "input"))
      (node (ref "IC12") (pin "3") (pinfunction "+IN_3") (pintype "input"))
      (node (ref "IC12") (pin "5") (pinfunction "+IN_5") (pintype "input"))
      (node (ref "IC13") (pin "3") (pinfunction "+IN_3") (pintype "input"))
      (node (ref "IC13") (pin "5") (pinfunction "+IN_5") (pintype "input"))
      (node (ref "IC2") (pin "2") (pinfunction "A_2") (pintype "passive"))
      (node (ref "IC3") (pin "6") (pinfunction "GND_6") (pintype "power_in"))
      (node (ref "IC4") (pin "1") (pinfunction "GND_1") (pintype "power_in"))
      (node (ref "IC5") (pin "2") (pinfunction "A_2") (pintype "passive"))
      (node (ref "IC7") (pin "3") (pinfunction "+IN_3") (pintype "input"))
      (node (ref "IC7") (pin "5") (pinfunction "+IN_5") (pintype "input"))
      (node (ref "IC8") (pin "3") (pinfunction "+IN_3") (pintype "input"))
      (node (ref "IC8") (pin "5") (pinfunction "+IN_5") (pintype "input"))
      (node (ref "IC9") (pin "3") (pinfunction "+IN_3") (pintype "input"))
      (node (ref "IC9") (pin "5") (pinfunction "+IN_5") (pintype "input"))
      (node (ref "J1") (pin "GND") (pinfunction "GND_GND") (pintype "passive"))
      (node (ref "J10") (pin "GND") (pinfunction "GND_GND") (pintype "passive"))
      (node (ref "J11") (pin "GND") (pinfunction "GND_GND") (pintype "passive"))
      (node (ref "J12") (pin "GND") (pinfunction "GND_GND") (pintype "passive"))
      (node (ref "J2") (pin "GND") (pinfunction "GND_GND") (pintype "passive"))
      (node (ref "J3") (pin "GND") (pinfunction "GND_GND") (pintype "passive"))
      (node (ref "J4") (pin "GND") (pinfunction "GND_GND") (pintype "passive"))
      (node (ref "J5") (pin "GND") (pinfunction "GND_GND") (pintype "passive"))
      (node (ref "J6") (pin "GND") (pinfunction "GND_GND") (pintype "passive"))
      (node (ref "J7") (pin "GND") (pinfunction "GND_GND") (pintype "passive"))
      (node (ref "J8") (pin "GND") (pinfunction "GND_GND") (pintype "passive"))
      (node (ref "J9") (pin "GND") (pinfunction "GND_GND") (pintype "passive"))
      (node (ref "JP2") (pin "3") (pinfunction "3_3") (pintype "passive"))
      (node (ref "JP2") (pin "4") (pinfunction "4_4") (pintype "passive"))
      (node (ref "JP2") (pin "5") (pinfunction "5_5") (pintype "passive"))
      (node (ref "JP2") (pin "6") (pinfunction "6_6") (pintype "passive"))
      (node (ref "JP2") (pin "7") (pinfunction "7_7") (pintype "passive"))
      (node (ref "JP2") (pin "8") (pinfunction "8_8") (pintype "passive"))
      (node (ref "JP4") (pin "3") (pinfunction "3_3") (pintype "passive"))
      (node (ref "JP4") (pin "5") (pinfunction "5_5") (pintype "passive"))
      (node (ref "JP4") (pin "9") (pinfunction "9_9") (pintype "passive"))
      (node (ref "LED5") (pin "GND") (pinfunction "C_GND") (pintype "bidirectional"))
      (node (ref "LED6") (pin "K") (pinfunction "C_K") (pintype "passive"))
      (node (ref "Q1") (pin "GND") (pinfunction "GND_GND") (pintype "bidirectional"))
      (node (ref "Q2") (pin "E") (pinfunction "E_E") (pintype "passive"))
      (node (ref "R10") (pin "1") (pinfunction "1_1") (pintype "passive"))
      (node (ref "R14") (pin "P$3") (pinfunction "A_P$3") (pintype "passive"))
      (node (ref "R2") (pin "2") (pinfunction "1_2") (pintype "bidirectional"))
      (node (ref "R2") (pin "4") (pinfunction "E_4") (pintype "bidirectional"))
      (node (ref "R24") (pin "1") (pinfunction "1_1") (pintype "passive"))
      (node (ref "R3") (pin "2") (pinfunction "1_2") (pintype "bidirectional"))
      (node (ref "R3") (pin "4") (pinfunction "E_4") (pintype "bidirectional"))
      (node (ref "R4") (pin "2") (pinfunction "1_2") (pintype "bidirectional"))
      (node (ref "R4") (pin "4") (pinfunction "E_4") (pintype "bidirectional"))
      (node (ref "R5") (pin "2") (pinfunction "1_2") (pintype "bidirectional"))
      (node (ref "R5") (pin "4") (pinfunction "E_4") (pintype "bidirectional"))
      (node (ref "R65") (pin "1") (pinfunction "1_1") (pintype "passive"))
      (node (ref "S1") (pin "1") (pinfunction "O_1") (pintype "passive"))
      (node (ref "SW3") (pin "1") (pinfunction "1_1") (pintype "passive"))
      (node (ref "SW3") (pin "2") (pinfunction "2_2") (pintype "passive"))
      (node (ref "SW4") (pin "1") (pinfunction "1_1") (pintype "passive"))
      (node (ref "SW4") (pin "2") (pinfunction "2_2") (pintype "passive"))
      (node (ref "U$1") (pin "C") (pinfunction "K_C") (pintype "bidirectional"))
      (node (ref "UC1") (pin "20") (pinfunction "PB2/BOOT1_20") (pintype "bidirectional"))
      (node (ref "UC1") (pin "23") (pinfunction "VSS_1_23") (pintype "power_in"))
      (node (ref "UC1") (pin "35") (pinfunction "VSS_2_35") (pintype "power_in"))
      (node (ref "UC1") (pin "47") (pinfunction "VSS_3_47") (pintype "power_in"))
      (node (ref "UC1") (pin "8") (pinfunction "VSS_A_8") (pintype "power_in"))
    )
    (net (code "18") (name "IN_1") (class "Default")
      (node (ref "J2") (pin "TIP") (pinfunction "TIP_TIP") (pintype "passive"))
      (node (ref "R54") (pin "1") (pinfunction "1_1") (pintype "passive"))
    )
    (net (code "19") (name "IN_2") (class "Default")
      (node (ref "J3") (pin "TIP") (pinfunction "TIP_TIP") (pintype "passive"))
      (node (ref "R33") (pin "1") (pinfunction "1_1") (pintype "passive"))
    )
    (net (code "20") (name "IN_3") (class "Default")
      (node (ref "J4") (pin "TIP") (pinfunction "TIP_TIP") (pintype "passive"))
      (node (ref "R36") (pin "1") (pinfunction "1_1") (pintype "passive"))
    )
    (net (code "21") (name "IN_4") (class "Default")
      (node (ref "J5") (pin "TIP") (pinfunction "TIP_TIP") (pintype "passive"))
      (node (ref "R57") (pin "1") (pinfunction "1_1") (pintype "passive"))
    )
    (net (code "22") (name "JTCK") (class "Default")
      (node (ref "JP4") (pin "4") (pinfunction "4_4") (pintype "passive"))
      (node (ref "UC1") (pin "37") (pinfunction "PA14/JTCK/SWCLK_37") (pintype "bidirectional"))
    )
    (net (code "23") (name "JTDI") (class "Default")
      (node (ref "JP4") (pin "8") (pinfunction "8_8") (pintype "passive"))
      (node (ref "UC1") (pin "38") (pinfunction "PA15/JTDI_38") (pintype "bidirectional"))
    )
    (net (code "24") (name "JTDO") (class "Default")
      (node (ref "JP4") (pin "6") (pinfunction "6_6") (pintype "passive"))
      (node (ref "UC1") (pin "39") (pinfunction "PB3/JTDO_39") (pintype "bidirectional"))
    )
    (net (code "25") (name "JTMS") (class "Default")
      (node (ref "JP4") (pin "2") (pinfunction "2_2") (pintype "passive"))
      (node (ref "UC1") (pin "34") (pinfunction "PA13/JTMS/SWDIO_34") (pintype "bidirectional"))
    )
    (net (code "26") (name "LED_B") (class "Default")
      (node (ref "R12") (pin "1") (pinfunction "1_1") (pintype "passive"))
      (node (ref "UC1") (pin "18") (pinfunction "PB0/ADC12_IN8/TIM3_CH3_18") (pintype "bidirectional"))
    )
    (net (code "27") (name "LED_CH1") (class "Default")
      (node (ref "R6") (pin "2") (pinfunction "2_2") (pintype "passive"))
      (node (ref "UC1") (pin "46") (pinfunction "PB9/TIM4_CH4_46") (pintype "input"))
    )
    (net (code "28") (name "LED_CH2") (class "Default")
      (node (ref "R7") (pin "2") (pinfunction "2_2") (pintype "passive"))
      (node (ref "UC1") (pin "45") (pinfunction "PB8/TIM4_CH3_45") (pintype "bidirectional"))
    )
    (net (code "29") (name "LED_CH3") (class "Default")
      (node (ref "R8") (pin "2") (pinfunction "2_2") (pintype "passive"))
      (node (ref "UC1") (pin "43") (pinfunction "PB7/I2C1_SDA/TIM4_CH2_43") (pintype "bidirectional"))
    )
    (net (code "30") (name "LED_CH4") (class "Default")
      (node (ref "R9") (pin "2") (pinfunction "2_2") (pintype "passive"))
      (node (ref "UC1") (pin "42") (pinfunction "PB6/I2C1_SCL/TIM4_CH1_42") (pintype "input"))
    )
    (net (code "31") (name "LED_FRAME") (class "Default")
      (node (ref "R16") (pin "1") (pinfunction "1_1") (pintype "passive"))
      (node (ref "UC1") (pin "41") (pinfunction "PB5/I2C1_SMBA_41") (pintype "input"))
    )
    (net (code "32") (name "LED_G") (class "Default")
      (node (ref "R11") (pin "1") (pinfunction "1_1") (pintype "passive"))
      (node (ref "UC1") (pin "17") (pinfunction "PA7/SPI1_MOSI/ADC12_IN7/TIM3_CH2_17") (pintype "bidirectional"))
    )
    (net (code "33") (name "LED_R") (class "Default")
      (node (ref "R13") (pin "1") (pinfunction "1_1") (pintype "passive"))
      (node (ref "UC1") (pin "19") (pinfunction "PB1/ADC12_IN9/TIM3_CH4_19") (pintype "bidirectional"))
    )
    (net (code "34") (name "MODULATION") (class "Default")
      (node (ref "D3") (pin "3") (pinfunction "AC_3") (pintype "passive"))
      (node (ref "R39") (pin "2") (pinfunction "2_2") (pintype "passive"))
      (node (ref "UC1") (pin "14") (pinfunction "PA4/SPI1_NSS/USART2_CK/ADC12_IN4_14") (pintype "bidirectional"))
    )
    (net (code "35") (name "Net-(B1-AC1)") (class "Default")
      (node (ref "B1") (pin "~1") (pinfunction "AC1_~1") (pintype "passive"))
      (node (ref "L1") (pin "2") (pinfunction "2_2") (pintype "passive"))
    )
    (net (code "36") (name "Net-(B1-AC2)") (class "Default")
      (node (ref "B1") (pin "~2") (pinfunction "AC2_~2") (pintype "passive"))
      (node (ref "L2") (pin "2") (pinfunction "2_2") (pintype "passive"))
    )
    (net (code "37") (name "Net-(C22-Pad1)") (class "Default")
      (node (ref "C22") (pin "1") (pinfunction "1_1") (pintype "passive"))
      (node (ref "R34") (pin "1") (pinfunction "1_1") (pintype "passive"))
    )
    (net (code "38") (name "Net-(C27-Pad1)") (class "Default")
      (node (ref "C27") (pin "1") (pinfunction "1_1") (pintype "passive"))
      (node (ref "R35") (pin "1") (pinfunction "1_1") (pintype "passive"))
    )
    (net (code "39") (name "Net-(C42-Pad1)") (class "Default")
      (node (ref "C42") (pin "1") (pinfunction "1_1") (pintype "passive"))
      (node (ref "R55") (pin "1") (pinfunction "1_1") (pintype "passive"))
    )
    (net (code "40") (name "Net-(C43-Pad1)") (class "Default")
      (node (ref "C43") (pin "1") (pinfunction "1_1") (pintype "passive"))
      (node (ref "R56") (pin "1") (pinfunction "1_1") (pintype "passive"))
    )
    (net (code "41") (name "Net-(IC3-OUTA)") (class "Default")
      (node (ref "IC3") (pin "2") (pinfunction "OUTA_2") (pintype "output"))
      (node (ref "R19") (pin "1") (pinfunction "1_1") (pintype "passive"))
    )
    (net (code "42") (name "Net-(IC3-OUTB)") (class "Default")
      (node (ref "IC3") (pin "3") (pinfunction "OUTB_3") (pintype "output"))
      (node (ref "R20") (pin "1") (pinfunction "1_1") (pintype "passive"))
    )
    (net (code "43") (name "Net-(IC3-OUTC)") (class "Default")
      (node (ref "IC3") (pin "4") (pinfunction "OUTC_4") (pintype "output"))
      (node (ref "R21") (pin "1") (pinfunction "1_1") (pintype "passive"))
    )
    (net (code "44") (name "Net-(IC3-OUTD)") (class "Default")
      (node (ref "IC3") (pin "5") (pinfunction "OUTD_5") (pintype "output"))
      (node (ref "R22") (pin "1") (pinfunction "1_1") (pintype "passive"))
    )
    (net (code "45") (name "Net-(IC5-C)") (class "Default")
      (node (ref "IC5") (pin "1") (pinfunction "C_1") (pintype "passive"))
      (node (ref "IC6") (pin "5") (pinfunction "+IN_5") (pintype "input"))
      (node (ref "R26") (pin "2") (pinfunction "2_2") (pintype "passive"))
      (node (ref "R27") (pin "2") (pinfunction "2_2") (pintype "passive"))
    )
    (net (code "46") (name "Net-(IC6A-+IN)") (class "Default")
      (node (ref "IC6") (pin "3") (pinfunction "+IN_3") (pintype "input"))
      (node (ref "R27") (pin "1") (pinfunction "1_1") (pintype "passive"))
      (node (ref "R65") (pin "2") (pinfunction "2_2") (pintype "passive"))
    )
    (net (code "47") (name "Net-(IC7A--IN)") (class "Default")
      (node (ref "C38") (pin "1") (pinfunction "1_1") (pintype "passive"))
      (node (ref "IC7") (pin "2") (pinfunction "-IN_2") (pintype "input"))
      (node (ref "R43") (pin "1") (pinfunction "1_1") (pintype "passive"))
      (node (ref "R44") (pin "2") (pinfunction "2_2") (pintype "passive"))
      (node (ref "R45") (pin "2") (pinfunction "2_2") (pintype "passive"))
      (node (ref "R46") (pin "2") (pinfunction "2_2") (pintype "passive"))
      (node (ref "R47") (pin "2") (pinfunction "2_2") (pintype "passive"))
    )
    (net (code "48") (name "Net-(IC7A-OUT)") (class "Default")
      (node (ref "C38") (pin "2") (pinfunction "2_2") (pintype "passive"))
      (node (ref "IC7") (pin "1") (pinfunction "OUT_1") (pintype "output"))
      (node (ref "R30") (pin "1") (pinfunction "1_1") (pintype "passive"))
      (node (ref "R43") (pin "2") (pinfunction "2_2") (pintype "passive"))
    )
    (net (code "49") (name "Net-(IC7B--IN)") (class "Default")
      (node (ref "C23") (pin "1") (pinfunction "1_1") (pintype "passive"))
      (node (ref "IC7") (pin "6") (pinfunction "-IN_6") (pintype "input"))
      (node (ref "R29") (pin "1") (pinfunction "1_1") (pintype "passive"))
      (node (ref "R30") (pin "2") (pinfunction "2_2") (pintype "passive"))
    )
    (net (code "50") (name "Net-(IC7B-OUT)") (class "Default")
      (node (ref "C23") (pin "2") (pinfunction "2_2") (pintype "passive"))
      (node (ref "IC7") (pin "7") (pinfunction "OUT_7") (pintype "output"))
      (node (ref "R28") (pin "1") (pinfunction "1_1") (pintype "passive"))
      (node (ref "R29") (pin "2") (pinfunction "2_2") (pintype "passive"))
    )
    (net (code "51") (name "Net-(IC8A--IN)") (class "Default")
      (node (ref "C39") (pin "1") (pinfunction "1_1") (pintype "passive"))
      (node (ref "IC8") (pin "2") (pinfunction "-IN_2") (pintype "input"))
      (node (ref "R49") (pin "1") (pinfunction "1_1") (pintype "passive"))
      (node (ref "R50") (pin "2") (pinfunction "2_2") (pintype "passive"))
    )
    (net (code "52") (name "Net-(IC8A-OUT)") (class "Default")
      (node (ref "C39") (pin "2") (pinfunction "2_2") (pintype "passive"))
      (node (ref "IC8") (pin "1") (pinfunction "OUT_1") (pintype "output"))
      (node (ref "R48") (pin "1") (pinfunction "1_1") (pintype "passive"))
      (node (ref "R49") (pin "2") (pinfunction "2_2") (pintype "passive"))
    )
    (net (code "53") (name "Net-(IC8B-OUT)") (class "Default")
      (node (ref "IC8") (pin "7") (pinfunction "OUT_7") (pintype "output"))
      (node (ref "R31") (pin "2") (pinfunction "2_2") (pintype "passive"))
      (node (ref "R50") (pin "1") (pinfunction "1_1") (pintype "passive"))
    )
    (net (code "54") (name "Net-(IC9A--IN)") (class "Default")
      (node (ref "C40") (pin "1") (pinfunction "1_1") (pintype "passive"))
      (node (ref "IC9") (pin "2") (pinfunction "-IN_2") (pintype "input"))
      (node (ref "R52") (pin "1") (pinfunction "1_1") (pintype "passive"))
      (node (ref "R53") (pin "2") (pinfunction "2_2") (pintype "passive"))
    )
    (net (code "55") (name "Net-(IC9A-OUT)") (class "Default")
      (node (ref "C40") (pin "2") (pinfunction "2_2") (pintype "passive"))
      (node (ref "IC9") (pin "1") (pinfunction "OUT_1") (pintype "output"))
      (node (ref "R51") (pin "1") (pinfunction "1_1") (pintype "passive"))
      (node (ref "R52") (pin "2") (pinfunction "2_2") (pintype "passive"))
    )
    (net (code "56") (name "Net-(IC9B-OUT)") (class "Default")
      (node (ref "IC9") (pin "7") (pinfunction "OUT_7") (pintype "output"))
      (node (ref "R32") (pin "2") (pinfunction "2_2") (pintype "passive"))
      (node (ref "R53") (pin "1") (pinfunction "1_1") (pintype "passive"))
    )
    (net (code "57") (name "Net-(IC10A-IN)") (class "Default")
      (node (ref "IC10") (pin "2") (pinfunction "IN_2") (pintype "input"))
      (node (ref "R54") (pin "2") (pinfunction "2_2") (pintype "passive"))
      (node (ref "R55") (pin "2") (pinfunction "2_2") (pintype "passive"))
    )
    (net (code "58") (name "Net-(IC10A-OUT)") (class "Default")
      (node (ref "IC10") (pin "4") (pinfunction "OUT_4") (pintype "output"))
      (node (ref "IC8") (pin "6") (pinfunction "-IN_6") (pintype "input"))
      (node (ref "R31") (pin "1") (pinfunction "1_1") (pintype "passive"))
    )
    (net (code "59") (name "Net-(IC10B-IN)") (class "Default")
      (node (ref "IC10") (pin "7") (pinfunction "IN_7") (pintype "input"))
      (node (ref "R56") (pin "2") (pinfunction "2_2") (pintype "passive"))
      (node (ref "R57") (pin "2") (pinfunction "2_2") (pintype "passive"))
    )
    (net (code "60") (name "Net-(IC10B-OUT)") (class "Default")
      (node (ref "IC10") (pin "5") (pinfunction "OUT_5") (pintype "output"))
      (node (ref "IC12") (pin "6") (pinfunction "-IN_6") (pintype "input"))
      (node (ref "R38") (pin "1") (pinfunction "1_1") (pintype "passive"))
    )
    (net (code "61") (name "Net-(IC10C-IN)") (class "Default")
      (node (ref "IC10") (pin "10") (pinfunction "IN_10") (pintype "input"))
      (node (ref "R35") (pin "2") (pinfunction "2_2") (pintype "passive"))
      (node (ref "R36") (pin "2") (pinfunction "2_2") (pintype "passive"))
    )
    (net (code "62") (name "Net-(IC10C-OUT)") (class "Default")
      (node (ref "IC10") (pin "12") (pinfunction "OUT_12") (pintype "output"))
      (node (ref "IC11") (pin "6") (pinfunction "-IN_6") (pintype "input"))
      (node (ref "R37") (pin "1") (pinfunction "1_1") (pintype "passive"))
    )
    (net (code "63") (name "Net-(IC10D-IN)") (class "Default")
      (node (ref "IC10") (pin "15") (pinfunction "IN_15") (pintype "input"))
      (node (ref "R33") (pin "2") (pinfunction "2_2") (pintype "passive"))
      (node (ref "R34") (pin "2") (pinfunction "2_2") (pintype "passive"))
    )
    (net (code "64") (name "Net-(IC10D-OUT)") (class "Default")
      (node (ref "IC10") (pin "13") (pinfunction "OUT_13") (pintype "output"))
      (node (ref "IC9") (pin "6") (pinfunction "-IN_6") (pintype "input"))
      (node (ref "R32") (pin "1") (pinfunction "1_1") (pintype "passive"))
    )
    (net (code "65") (name "Net-(IC11A--IN)") (class "Default")
      (node (ref "C44") (pin "1") (pinfunction "1_1") (pintype "passive"))
      (node (ref "IC11") (pin "2") (pinfunction "-IN_2") (pintype "input"))
      (node (ref "R59") (pin "1") (pinfunction "1_1") (pintype "passive"))
      (node (ref "R60") (pin "2") (pinfunction "2_2") (pintype "passive"))
    )
    (net (code "66") (name "Net-(IC11A-OUT)") (class "Default")
      (node (ref "C44") (pin "2") (pinfunction "2_2") (pintype "passive"))
      (node (ref "IC11") (pin "1") (pinfunction "OUT_1") (pintype "output"))
      (node (ref "R58") (pin "1") (pinfunction "1_1") (pintype "passive"))
      (node (ref "R59") (pin "2") (pinfunction "2_2") (pintype "passive"))
    )
    (net (code "67") (name "Net-(IC11B-OUT)") (class "Default")
      (node (ref "IC11") (pin "7") (pinfunction "OUT_7") (pintype "output"))
      (node (ref "R37") (pin "2") (pinfunction "2_2") (pintype "passive"))
      (node (ref "R60") (pin "1") (pinfunction "1_1") (pintype "passive"))
    )
    (net (code "68") (name "Net-(IC12A--IN)") (class "Default")
      (node (ref "C46") (pin "1") (pinfunction "1_1") (pintype "passive"))
      (node (ref "IC12") (pin "2") (pinfunction "-IN_2") (pintype "input"))
      (node (ref "R62") (pin "1") (pinfunction "1_1") (pintype "passive"))
      (node (ref "R63") (pin "2") (pinfunction "2_2") (pintype "passive"))
    )
    (net (code "69") (name "Net-(IC12A-OUT)") (class "Default")
      (node (ref "C46") (pin "2") (pinfunction "2_2") (pintype "passive"))
      (node (ref "IC12") (pin "1") (pinfunction "OUT_1") (pintype "output"))
      (node (ref "R61") (pin "1") (pinfunction "1_1") (pintype "passive"))
      (node (ref "R62") (pin "2") (pinfunction "2_2") (pintype "passive"))
    )
    (net (code "70") (name "Net-(IC12B-OUT)") (class "Default")
      (node (ref "IC12") (pin "7") (pinfunction "OUT_7") (pintype "output"))
      (node (ref "R38") (pin "2") (pinfunction "2_2") (pintype "passive"))
      (node (ref "R63") (pin "1") (pinfunction "1_1") (pintype "passive"))
    )
    (net (code "71") (name "Net-(IC13A--IN)") (class "Default")
      (node (ref "IC13") (pin "2") (pinfunction "-IN_2") (pintype "input"))
      (node (ref "R15") (pin "P$3") (pinfunction "3_P$3") (pintype "passive"))
      (node (ref "R64") (pin "1") (pinfunction "1_1") (pintype "passive"))
    )
    (net (code "72") (name "Net-(IC13A-OUT)") (class "Default")
      (node (ref "IC13") (pin "1") (pinfunction "OUT_1") (pintype "output"))
      (node (ref "R41") (pin "1") (pinfunction "1_1") (pintype "passive"))
      (node (ref "R64") (pin "2") (pinfunction "2_2") (pintype "passive"))
    )
    (net (code "73") (name "Net-(IC13B--IN)") (class "Default")
      (node (ref "C31") (pin "1") (pinfunction "1_1") (pintype "passive"))
      (node (ref "IC13") (pin "6") (pinfunction "-IN_6") (pintype "input"))
      (node (ref "R15") (pin "P$1") (pinfunction "1_P$1") (pintype "passive"))
      (node (ref "R40") (pin "1") (pinfunction "1_1") (pintype "passive"))
      (node (ref "R41") (pin "2") (pinfunction "2_2") (pintype "passive"))
      (node (ref "R42") (pin "2") (pinfunction "2_2") (pintype "passive"))
    )
    (net (code "74") (name "Net-(IC13B-OUT)") (class "Default")
      (node (ref "C31") (pin "2") (pinfunction "2_2") (pintype "passive"))
      (node (ref "IC13") (pin "7") (pinfunction "OUT_7") (pintype "output"))
      (node (ref "R39") (pin "1") (pinfunction "1_1") (pintype "passive"))
      (node (ref "R40") (pin "2") (pinfunction "2_2") (pintype "passive"))
    )
    (net (code "75") (name "Net-(J6-PadTIP)") (class "Default")
      (node (ref "J6") (pin "TIP") (pinfunction "TIP_TIP") (pintype "passive"))
      (node (ref "R18") (pin "1") (pinfunction "1_1") (pintype "passive"))
    )
    (net (code "76") (name "Net-(J7-PadTIP)") (class "Default")
      (node (ref "J7") (pin "TIP") (pinfunction "TIP_TIP") (pintype "passive"))
      (node (ref "R28") (pin "2") (pinfunction "2_2") (pintype "passive"))
    )
    (net (code "77") (name "Net-(J8-PadTIP)") (class "Default")
      (node (ref "J8") (pin "TIP") (pinfunction "TIP_TIP") (pintype "passive"))
      (node (ref "R48") (pin "2") (pinfunction "2_2") (pintype "passive"))
    )
    (net (code "78") (name "Net-(J9-PadTIP)") (class "Default")
      (node (ref "J9") (pin "TIP") (pinfunction "TIP_TIP") (pintype "passive"))
      (node (ref "R51") (pin "2") (pinfunction "2_2") (pintype "passive"))
    )
    (net (code "79") (name "Net-(J10-PadTIP)") (class "Default")
      (node (ref "J10") (pin "TIP") (pinfunction "TIP_TIP") (pintype "passive"))
      (node (ref "R58") (pin "2") (pinfunction "2_2") (pintype "passive"))
    )
    (net (code "80") (name "Net-(J11-PadTIP)") (class "Default")
      (node (ref "J11") (pin "TIP") (pinfunction "TIP_TIP") (pintype "passive"))
      (node (ref "R61") (pin "2") (pinfunction "2_2") (pintype "passive"))
    )
    (net (code "81") (name "Net-(J12-PadTIP)") (class "Default")
      (node (ref "J12") (pin "TIP") (pinfunction "TIP_TIP") (pintype "passive"))
      (node (ref "Q2") (pin "C") (pinfunction "C_C") (pintype "passive"))
      (node (ref "R24") (pin "2") (pinfunction "2_2") (pintype "passive"))
      (node (ref "R25") (pin "1") (pinfunction "1_1") (pintype "passive"))
    )
    (net (code "82") (name "Net-(JP2-Pad1)") (class "Default")
      (node (ref "JP2") (pin "1") (pinfunction "1_1") (pintype "passive"))
      (node (ref "JP2") (pin "2") (pinfunction "2_2") (pintype "passive"))
      (node (ref "L1") (pin "1") (pinfunction "1_1") (pintype "passive"))
    )
    (net (code "83") (name "Net-(JP2-Pad10)") (class "Default")
      (node (ref "JP2") (pin "10") (pinfunction "10_10") (pintype "passive"))
      (node (ref "JP2") (pin "9") (pinfunction "9_9") (pintype "passive"))
      (node (ref "L2") (pin "1") (pinfunction "1_1") (pintype "passive"))
    )
    (net (code "84") (name "Net-(LED5-PadBLU)") (class "Default")
      (node (ref "LED5") (pin "BLU") (pinfunction "BLU_BLU") (pintype "bidirectional"))
      (node (ref "R12") (pin "2") (pinfunction "2_2") (pintype "passive"))
    )
    (net (code "85") (name "Net-(LED5-PadGRN)") (class "Default")
      (node (ref "LED5") (pin "GRN") (pinfunction "GRN_GRN") (pintype "bidirectional"))
      (node (ref "R11") (pin "2") (pinfunction "2_2") (pintype "passive"))
    )
    (net (code "86") (name "Net-(LED5-PadRED)") (class "Default")
      (node (ref "LED5") (pin "RED") (pinfunction "RED_RED") (pintype "bidirectional"))
      (node (ref "R13") (pin "2") (pinfunction "2_2") (pintype "passive"))
    )
    (net (code "87") (name "Net-(LED6-PadA)") (class "Default")
      (node (ref "LED6") (pin "A") (pinfunction "A_A") (pintype "passive"))
      (node (ref "R16") (pin "2") (pinfunction "2_2") (pintype "passive"))
    )
    (net (code "88") (name "Net-(Q2-PadB)") (class "Default")
      (node (ref "Q2") (pin "B") (pinfunction "B_B") (pintype "passive"))
      (node (ref "R23") (pin "2") (pinfunction "2_2") (pintype "passive"))
    )
    (net (code "89") (name "Net-(R2-B)") (class "Default")
      (node (ref "R2") (pin "5") (pinfunction "B_5") (pintype "bidirectional"))
      (node (ref "R6") (pin "1") (pinfunction "1_1") (pintype "passive"))
    )
    (net (code "90") (name "Net-(R3-B)") (class "Default")
      (node (ref "R3") (pin "5") (pinfunction "B_5") (pintype "bidirectional"))
      (node (ref "R7") (pin "1") (pinfunction "1_1") (pintype "passive"))
    )
    (net (code "91") (name "Net-(R4-B)") (class "Default")
      (node (ref "R4") (pin "5") (pinfunction "B_5") (pintype "bidirectional"))
      (node (ref "R8") (pin "1") (pinfunction "1_1") (pintype "passive"))
    )
    (net (code "92") (name "Net-(R5-B)") (class "Default")
      (node (ref "R5") (pin "5") (pinfunction "B_5") (pintype "bidirectional"))
      (node (ref "R9") (pin "1") (pinfunction "1_1") (pintype "passive"))
    )
    (net (code "93") (name "Net-(R15-2)") (class "Default")
      (node (ref "R15") (pin "P$2") (pinfunction "2_P$2") (pintype "passive"))
      (node (ref "R18") (pin "2") (pinfunction "2_2") (pintype "passive"))
    )
    (net (code "94") (name "Net-(S1-P)") (class "Default")
      (node (ref "J1") (pin "NORM") (pinfunction "NORM_NORM") (pintype "passive"))
      (node (ref "S1") (pin "2") (pinfunction "P_2") (pintype "passive"))
    )
    (net (code "95") (name "Net-(S1-S)") (class "Default")
      (node (ref "JP1") (pin "2") (pinfunction "2_2") (pintype "passive"))
      (node (ref "S1") (pin "3") (pinfunction "S_3") (pintype "passive"))
    )
    (net (code "96") (name "Net-(UC1-PD0-OSC_IN)") (class "Default")
      (node (ref "Q1") (pin "X1") (pinfunction "X1_X1") (pintype "bidirectional"))
      (node (ref "UC1") (pin "5") (pinfunction "PD0-OSC_IN_5") (pintype "input"))
    )
    (net (code "97") (name "Net-(UC1-PD1-OSC_OUT)") (class "Default")
      (node (ref "Q1") (pin "X2") (pinfunction "X2_X2") (pintype "bidirectional"))
      (node (ref "UC1") (pin "6") (pinfunction "PD1-OSC_OUT_6") (pintype "input"))
    )
    (net (code "98") (name "PAN") (class "Default")
      (node (ref "J1") (pin "TIP") (pinfunction "TIP_TIP") (pintype "passive"))
      (node (ref "J2") (pin "NORM") (pinfunction "NORM_NORM") (pintype "passive"))
      (node (ref "J3") (pin "NORM") (pinfunction "NORM_NORM") (pintype "passive"))
      (node (ref "J4") (pin "NORM") (pinfunction "NORM_NORM") (pintype "passive"))
      (node (ref "J5") (pin "NORM") (pinfunction "NORM_NORM") (pintype "passive"))
    )
    (net (code "99") (name "POT_CH1") (class "Default")
      (node (ref "R2") (pin "1") (pinfunction "2_1") (pintype "bidirectional"))
      (node (ref "UC1") (pin "10") (pinfunction "PA0_WKUP/USART2_CTS/ADC12_IN0/TIM2_CH1_ETR_10") (pintype "bidirectional"))
    )
    (net (code "100") (name "POT_CH2") (class "Default")
      (node (ref "R3") (pin "1") (pinfunction "2_1") (pintype "bidirectional"))
      (node (ref "UC1") (pin "11") (pinfunction "PA1/USART2_RTS/ADC12_IN1/TIM2_CH2_11") (pintype "bidirectional"))
    )
    (net (code "101") (name "POT_CH3") (class "Default")
      (node (ref "R4") (pin "1") (pinfunction "2_1") (pintype "bidirectional"))
      (node (ref "UC1") (pin "12") (pinfunction "PA2/USART2_TX/ADC12_IN2/TIM2_CH3_12") (pintype "bidirectional"))
    )
    (net (code "102") (name "POT_CH4") (class "Default")
      (node (ref "R5") (pin "1") (pinfunction "2_1") (pintype "bidirectional"))
      (node (ref "UC1") (pin "13") (pinfunction "PA3/USART2_RX/ADC12_IN3/TIM2_CH4_13") (pintype "bidirectional"))
    )
    (net (code "103") (name "POT_FRAME") (class "Default")
      (node (ref "R14") (pin "P$2") (pinfunction "S_P$2") (pintype "passive"))
      (node (ref "UC1") (pin "15") (pinfunction "PA5/SPI1_SCK/ADC12_IN5_15") (pintype "bidirectional"))
    )
    (net (code "104") (name "RESET") (class "Default")
      (node (ref "JP4") (pin "10") (pinfunction "10_10") (pintype "passive"))
      (node (ref "R1") (pin "1") (pinfunction "1_1") (pintype "passive"))
      (node (ref "UC1") (pin "7") (pinfunction "NRST_7") (pintype "input"))
    )
    (net (code "105") (name "RX") (class "Default")
      (node (ref "UC1") (pin "31") (pinfunction "PA10/USART1_RX/TIM1_CH3_31") (pintype "bidirectional"))
    )
    (net (code "106") (name "TX") (class "Default")
      (node (ref "UC1") (pin "30") (pinfunction "PA9/USART1_TX/TIM1_CH2_30") (pintype "input"))
    )
    (net (code "107") (name "VCA_1") (class "Default")
      (node (ref "J8") (pin "NORM") (pinfunction "NORM_NORM") (pintype "passive"))
      (node (ref "R44") (pin "1") (pinfunction "1_1") (pintype "passive"))
    )
    (net (code "108") (name "VCA_2") (class "Default")
      (node (ref "J9") (pin "NORM") (pinfunction "NORM_NORM") (pintype "passive"))
      (node (ref "R47") (pin "1") (pinfunction "1_1") (pintype "passive"))
    )
    (net (code "109") (name "VCA_3") (class "Default")
      (node (ref "J10") (pin "NORM") (pinfunction "NORM_NORM") (pintype "passive"))
      (node (ref "R46") (pin "1") (pinfunction "1_1") (pintype "passive"))
    )
    (net (code "110") (name "VCA_4") (class "Default")
      (node (ref "J11") (pin "NORM") (pinfunction "NORM_NORM") (pintype "passive"))
      (node (ref "R45") (pin "1") (pinfunction "1_1") (pintype "passive"))
    )
    (net (code "111") (name "VCC") (class "Default")
      (node (ref "B1") (pin "+") (pinfunction "+_+") (pintype "passive"))
      (node (ref "C11") (pin "+") (pinfunction "+_+") (pintype "passive"))
      (node (ref "C24") (pin "1") (pinfunction "1_1") (pintype "passive"))
      (node (ref "C25") (pin "1") (pinfunction "1_1") (pintype "passive"))
      (node (ref "C26") (pin "1") (pinfunction "1_1") (pintype "passive"))
      (node (ref "C29") (pin "1") (pinfunction "1_1") (pintype "passive"))
      (node (ref "C30") (pin "1") (pinfunction "1_1") (pintype "passive"))
      (node (ref "C34") (pin "1") (pinfunction "1_1") (pintype "passive"))
      (node (ref "C35") (pin "1") (pinfunction "1_1") (pintype "passive"))
      (node (ref "C4") (pin "+") (pinfunction "+_+") (pintype "passive"))
      (node (ref "IC1") (pin "3") (pinfunction "VIN_3") (pintype "input"))
      (node (ref "IC10") (pin "16") (pinfunction "V+_16") (pintype "power_in"))
      (node (ref "IC11") (pin "8") (pinfunction "V+_8") (pintype "power_in"))
      (node (ref "IC12") (pin "8") (pinfunction "V+_8") (pintype "power_in"))
      (node (ref "IC13") (pin "8") (pinfunction "V+_8") (pintype "power_in"))
      (node (ref "IC4") (pin "3") (pinfunction "VIN_3") (pintype "input"))
      (node (ref "IC6") (pin "8") (pinfunction "V+_8") (pintype "power_in"))
      (node (ref "IC7") (pin "8") (pinfunction "V+_8") (pintype "power_in"))
      (node (ref "IC8") (pin "8") (pinfunction "V+_8") (pintype "power_in"))
      (node (ref "IC9") (pin "8") (pinfunction "V+_8") (pintype "power_in"))
      (node (ref "R25") (pin "2") (pinfunction "2_2") (pintype "passive"))
      (node (ref "R26") (pin "1") (pinfunction "1_1") (pintype "passive"))
    )
    (net (code "112") (name "VEE") (class "Default")
      (node (ref "B1") (pin "-") (pinfunction "-_-") (pintype "passive"))
      (node (ref "C21") (pin "-") (pinfunction "-_-") (pintype "passive"))
      (node (ref "C28") (pin "2") (pinfunction "2_2") (pintype "passive"))
      (node (ref "C36") (pin "2") (pinfunction "2_2") (pintype "passive"))
      (node (ref "C37") (pin "2") (pinfunction "2_2") (pintype "passive"))
      (node (ref "C41") (pin "2") (pinfunction "2_2") (pintype "passive"))
      (node (ref "C45") (pin "2") (pinfunction "2_2") (pintype "passive"))
      (node (ref "C47") (pin "2") (pinfunction "2_2") (pintype "passive"))
      (node (ref "C48") (pin "2") (pinfunction "2_2") (pintype "passive"))
      (node (ref "IC10") (pin "9") (pinfunction "V-_9") (pintype "power_in"))
      (node (ref "IC11") (pin "4") (pinfunction "V-_4") (pintype "power_in"))
      (node (ref "IC12") (pin "4") (pinfunction "V-_4") (pintype "power_in"))
      (node (ref "IC13") (pin "4") (pinfunction "V-_4") (pintype "power_in"))
      (node (ref "IC6") (pin "4") (pinfunction "V-_4") (pintype "power_in"))
      (node (ref "IC7") (pin "4") (pinfunction "V-_4") (pintype "power_in"))
      (node (ref "IC8") (pin "4") (pinfunction "V-_4") (pintype "power_in"))
      (node (ref "IC9") (pin "4") (pinfunction "V-_4") (pintype "power_in"))
      (node (ref "R42") (pin "1") (pinfunction "1_1") (pintype "passive"))
      (node (ref "U$1") (pin "A") (pinfunction "A_A") (pintype "bidirectional"))
    )
    (net (code "113") (name "unconnected-(IC10E-MODE-Pad1)") (class "Default")
      (node (ref "IC10") (pin "1") (pinfunction "MODE_1") (pintype "input"))
    )
    (net (code "114") (name "unconnected-(J6-PadNORM)") (class "Default")
      (node (ref "J6") (pin "NORM") (pinfunction "NORM_NORM") (pintype "passive"))
    )
    (net (code "115") (name "unconnected-(J7-PadNORM)") (class "Default")
      (node (ref "J7") (pin "NORM") (pinfunction "NORM_NORM") (pintype "passive"))
    )
    (net (code "116") (name "unconnected-(J12-PadNORM)") (class "Default")
      (node (ref "J12") (pin "NORM") (pinfunction "NORM_NORM") (pintype "passive"))
    )
    (net (code "117") (name "unconnected-(JP4-Pad7)") (class "Default")
      (node (ref "JP4") (pin "7") (pinfunction "7_7") (pintype "passive"))
    )
    (net (code "118") (name "unconnected-(R2-L-Pad3)") (class "Default")
      (node (ref "R2") (pin "3") (pinfunction "L_3") (pintype "bidirectional"))
    )
    (net (code "119") (name "unconnected-(R3-L-Pad3)") (class "Default")
      (node (ref "R3") (pin "3") (pinfunction "L_3") (pintype "bidirectional"))
    )
    (net (code "120") (name "unconnected-(R4-L-Pad3)") (class "Default")
      (node (ref "R4") (pin "3") (pinfunction "L_3") (pintype "bidirectional"))
    )
    (net (code "121") (name "unconnected-(R5-L-Pad3)") (class "Default")
      (node (ref "R5") (pin "3") (pinfunction "L_3") (pintype "bidirectional"))
    )
    (net (code "122") (name "unconnected-(UC1-PA8{slash}USART1_CK{slash}TIM1_CH1{slash}MCO-Pad29)") (class "Default")
      (node (ref "UC1") (pin "29") (pinfunction "PA8/USART1_CK/TIM1_CH1/MCO_29") (pintype "bidirectional"))
    )
    (net (code "123") (name "unconnected-(UC1-PA11{slash}USART1_CTS{slash}CAN_RX{slash}TIM1_CH4{slash}USBDM-Pad32)") (class "Default")
      (node (ref "UC1") (pin "32") (pinfunction "PA11/USART1_CTS/CAN_RX/TIM1_CH4/USBDM_32") (pintype "bidirectional"))
    )
    (net (code "124") (name "unconnected-(UC1-PA12{slash}USART1_RTS{slash}CAN_TX{slash}TIM1_ETR{slash}USBDP-Pad33)") (class "Default")
      (node (ref "UC1") (pin "33") (pinfunction "PA12/USART1_RTS/CAN_TX/TIM1_ETR/USBDP_33") (pintype "bidirectional"))
    )
    (net (code "125") (name "unconnected-(UC1-PB4{slash}NJTRST-Pad40)") (class "Default")
      (node (ref "UC1") (pin "40") (pinfunction "PB4/NJTRST_40") (pintype "bidirectional"))
    )
    (net (code "126") (name "unconnected-(UC1-PB14{slash}SPI2_MISO{slash}USART3_RTS{slash}TIM1_CH2N-Pad27)") (class "Default")
      (node (ref "UC1") (pin "27") (pinfunction "PB14/SPI2_MISO/USART3_RTS/TIM1_CH2N_27") (pintype "input"))
    )
    (net (code "127") (name "unconnected-(UC1-PC13-TAMPER-RTC-Pad2)") (class "Default")
      (node (ref "UC1") (pin "2") (pinfunction "PC13-TAMPER-RTC_2") (pintype "input"))
    )
    (net (code "128") (name "unconnected-(UC1-PC14-OSC32_IN-Pad3)") (class "Default")
      (node (ref "UC1") (pin "3") (pinfunction "PC14-OSC32_IN_3") (pintype "input"))
    )
    (net (code "129") (name "unconnected-(UC1-PC15-OSC32_OUT-Pad4)") (class "Default")
      (node (ref "UC1") (pin "4") (pinfunction "PC15-OSC32_OUT_4") (pintype "input"))
    )
  )
)
